# BatteryBoardV3.net
KiCad netlist of a schematic drawn in EAGLE
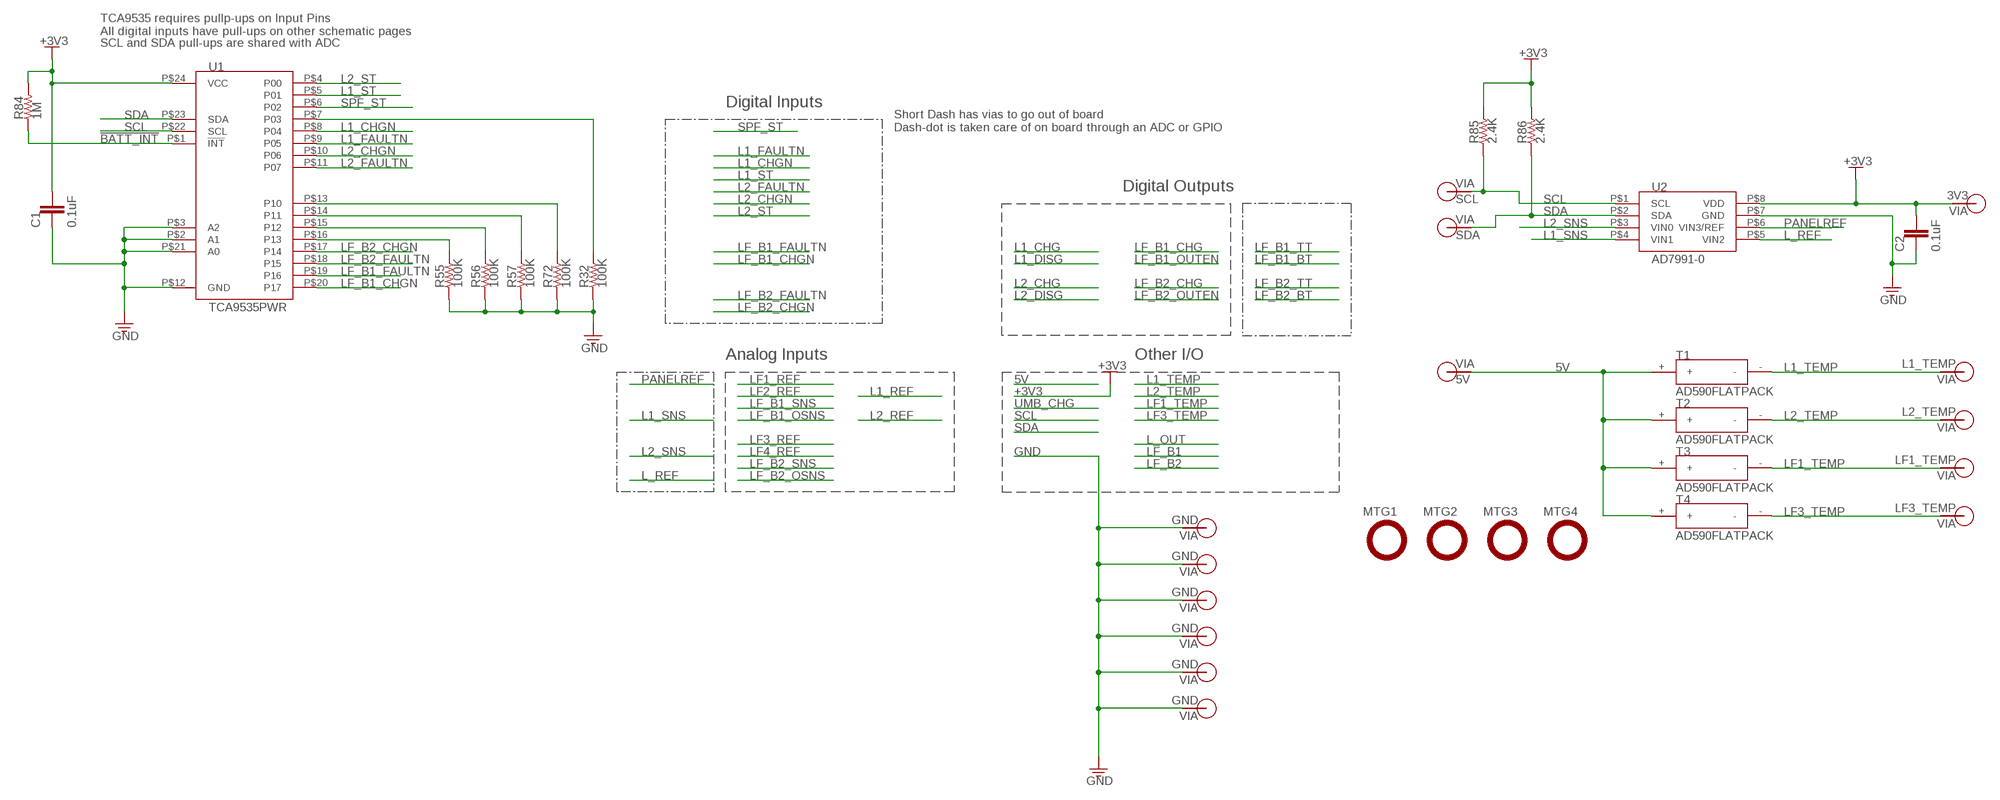
[diagram p0: schematic, sheet 1]
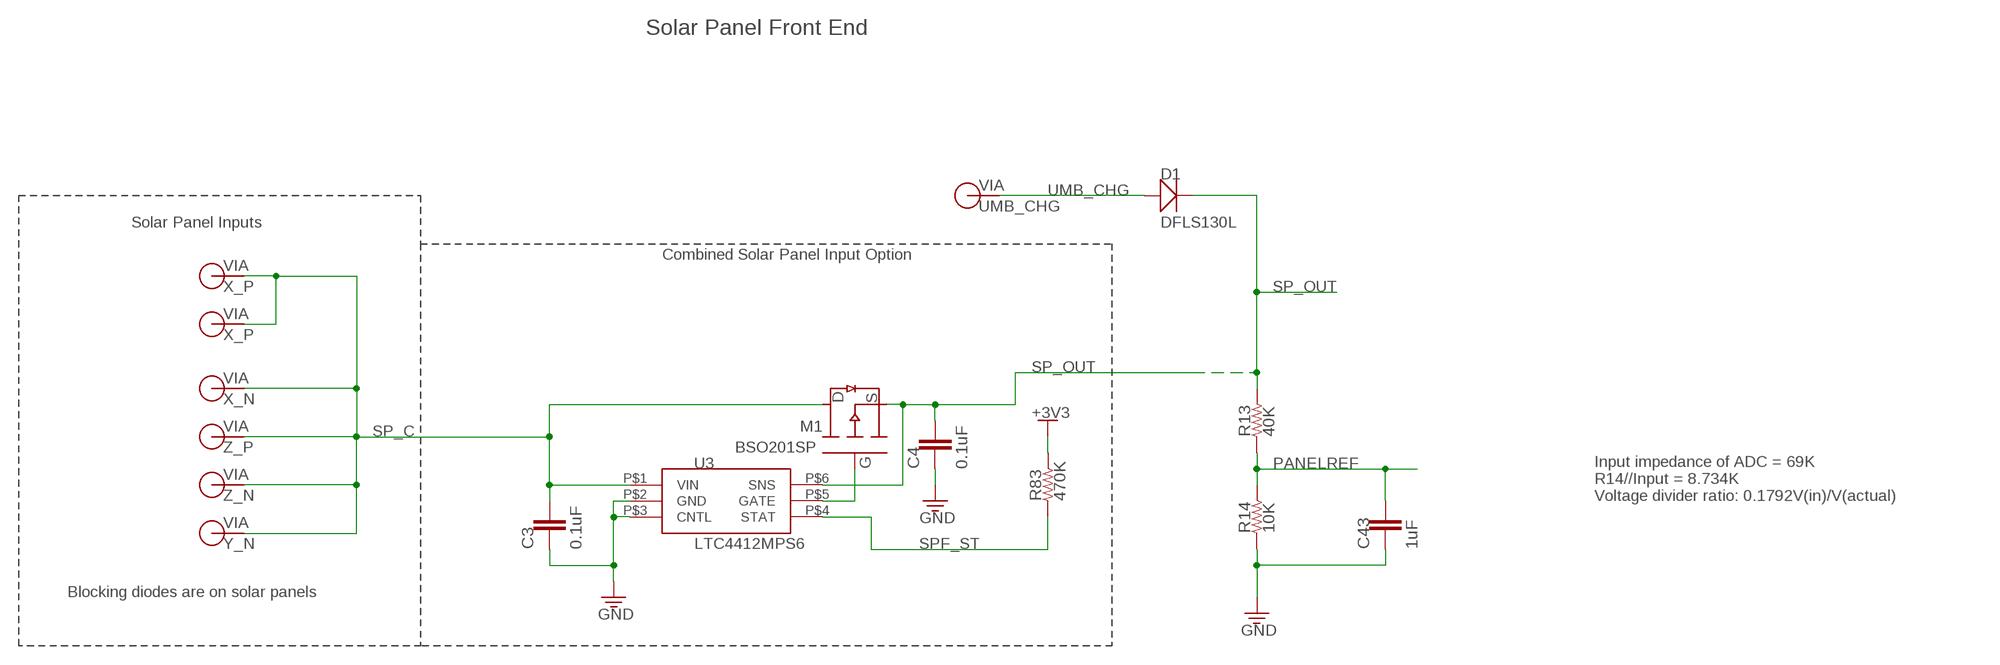
[diagram p1: schematic, sheet 2]
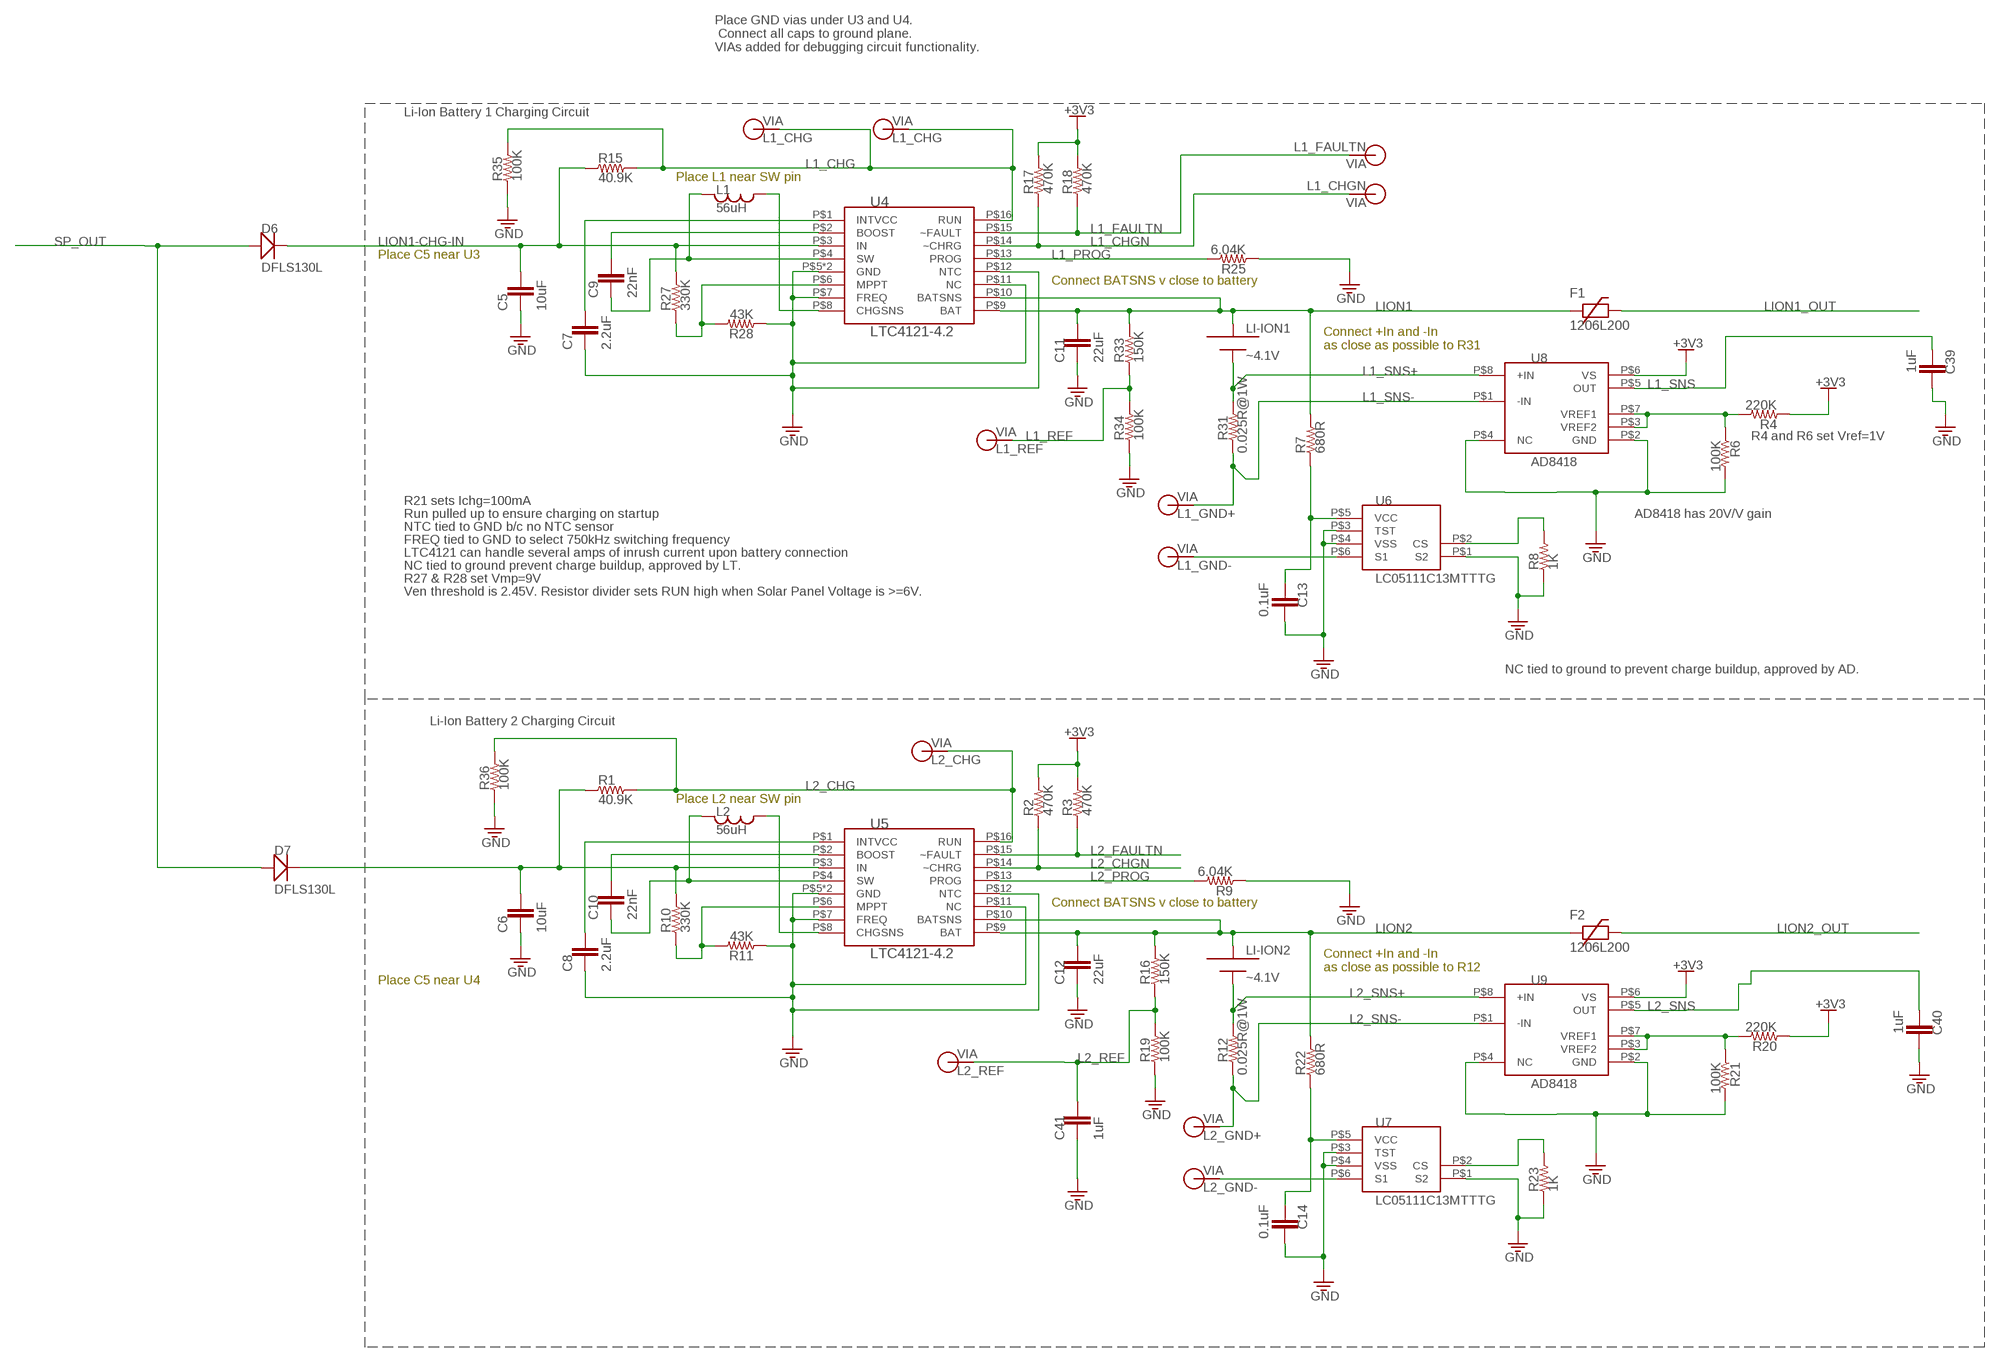
[diagram p2: schematic, sheet 3]
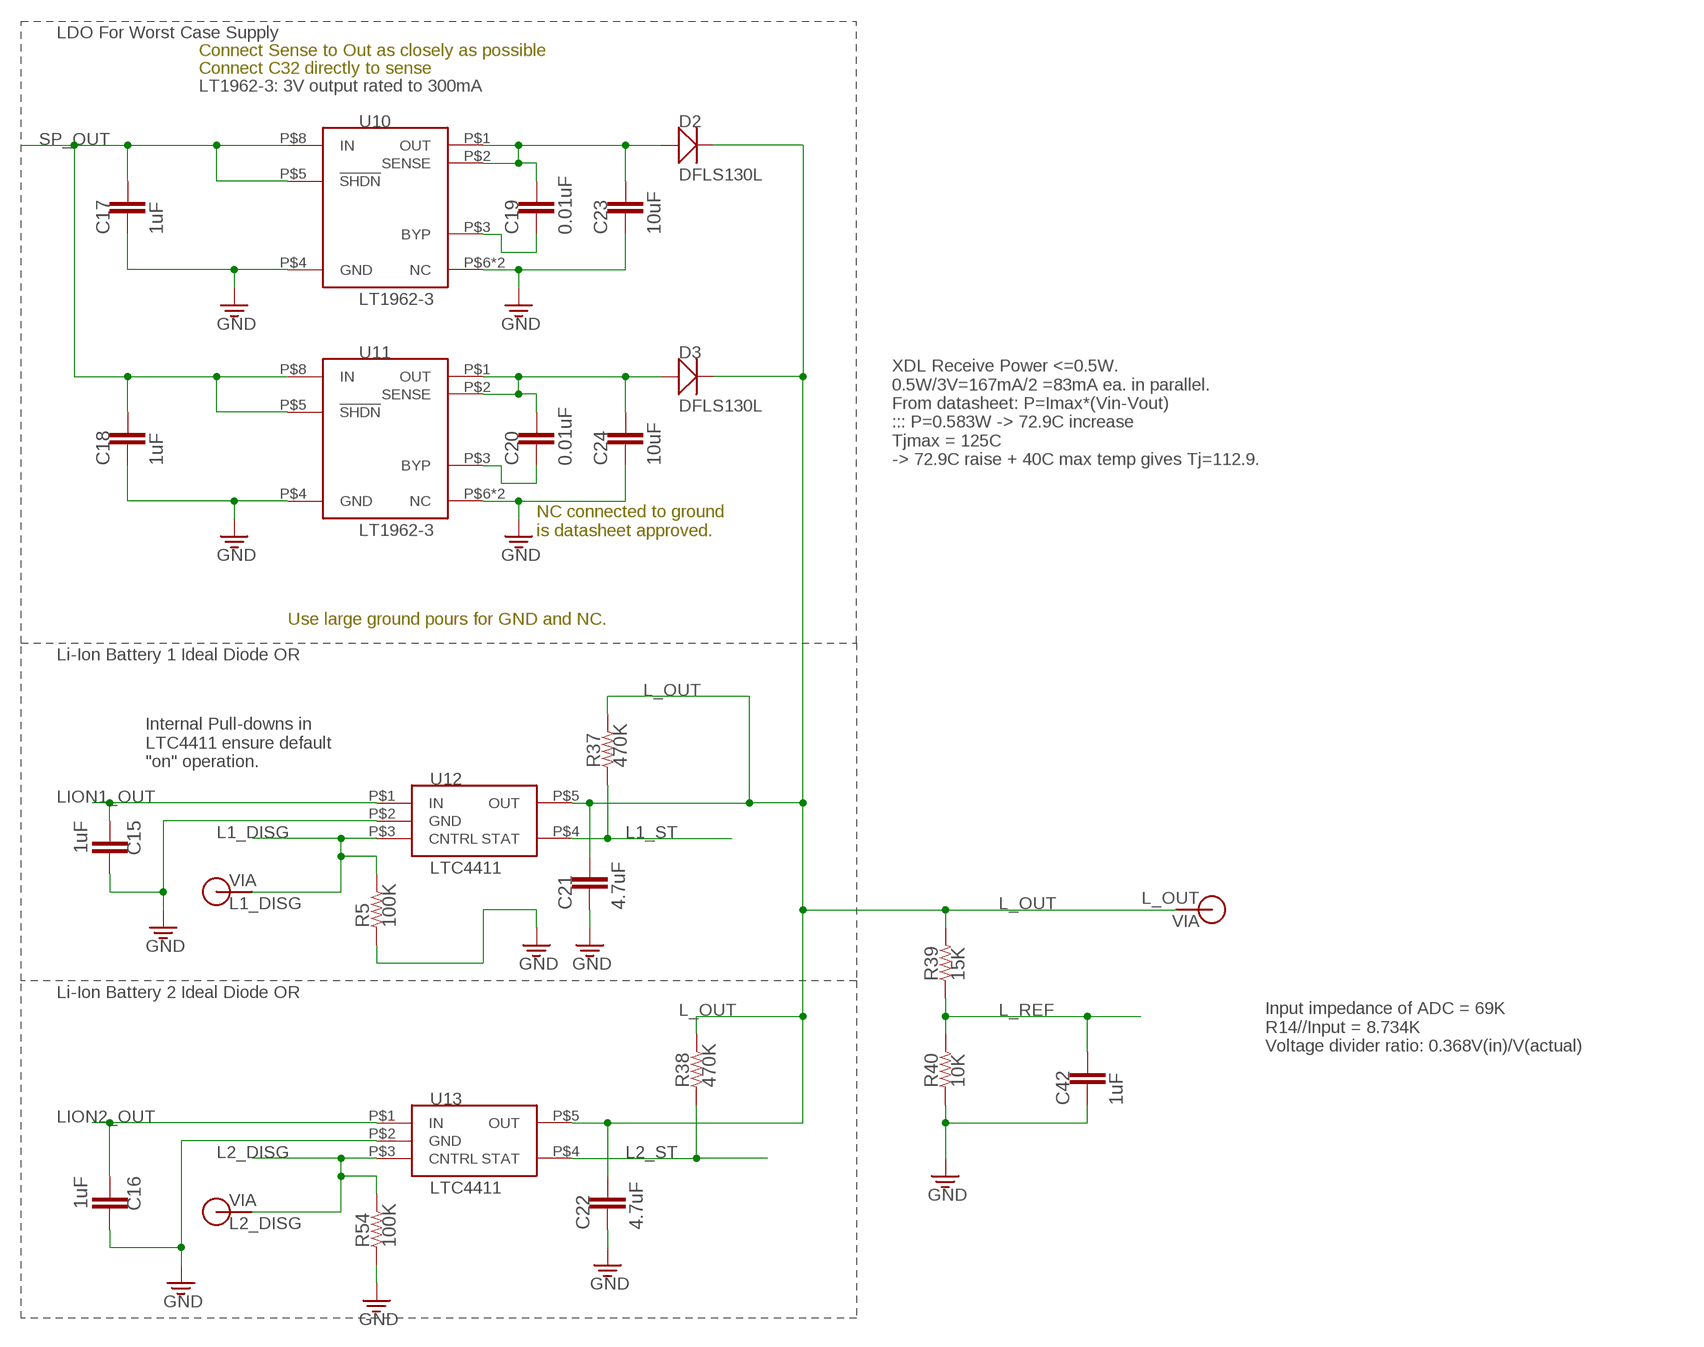
[diagram p3: schematic, sheet 4]
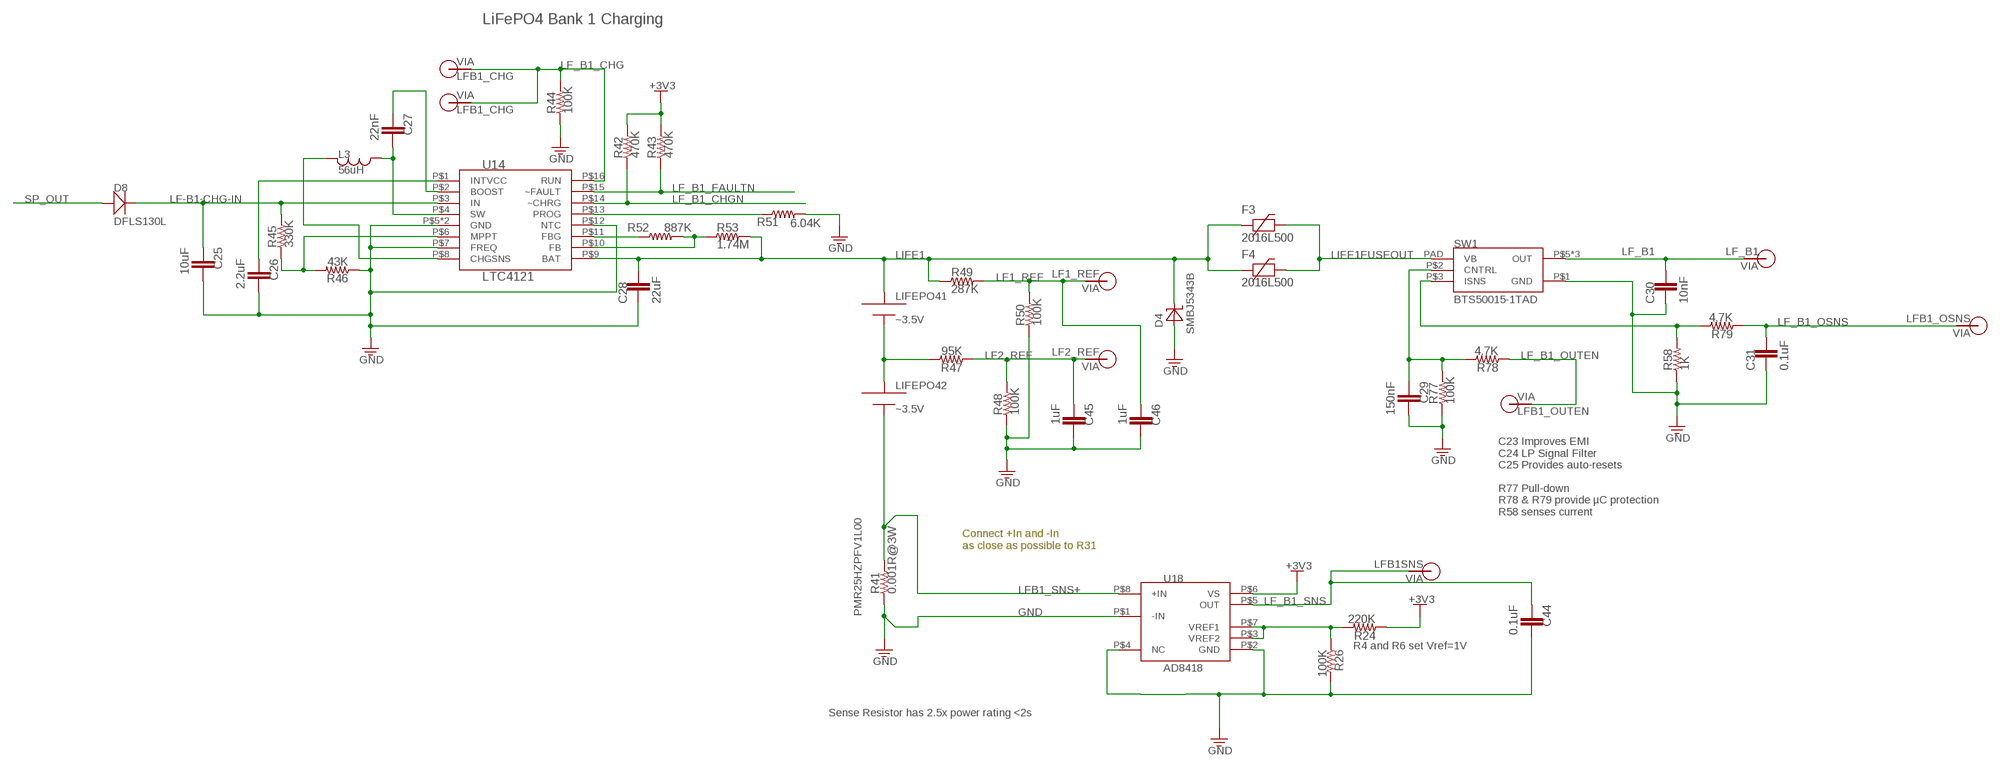
[diagram p4: schematic, sheet 5]
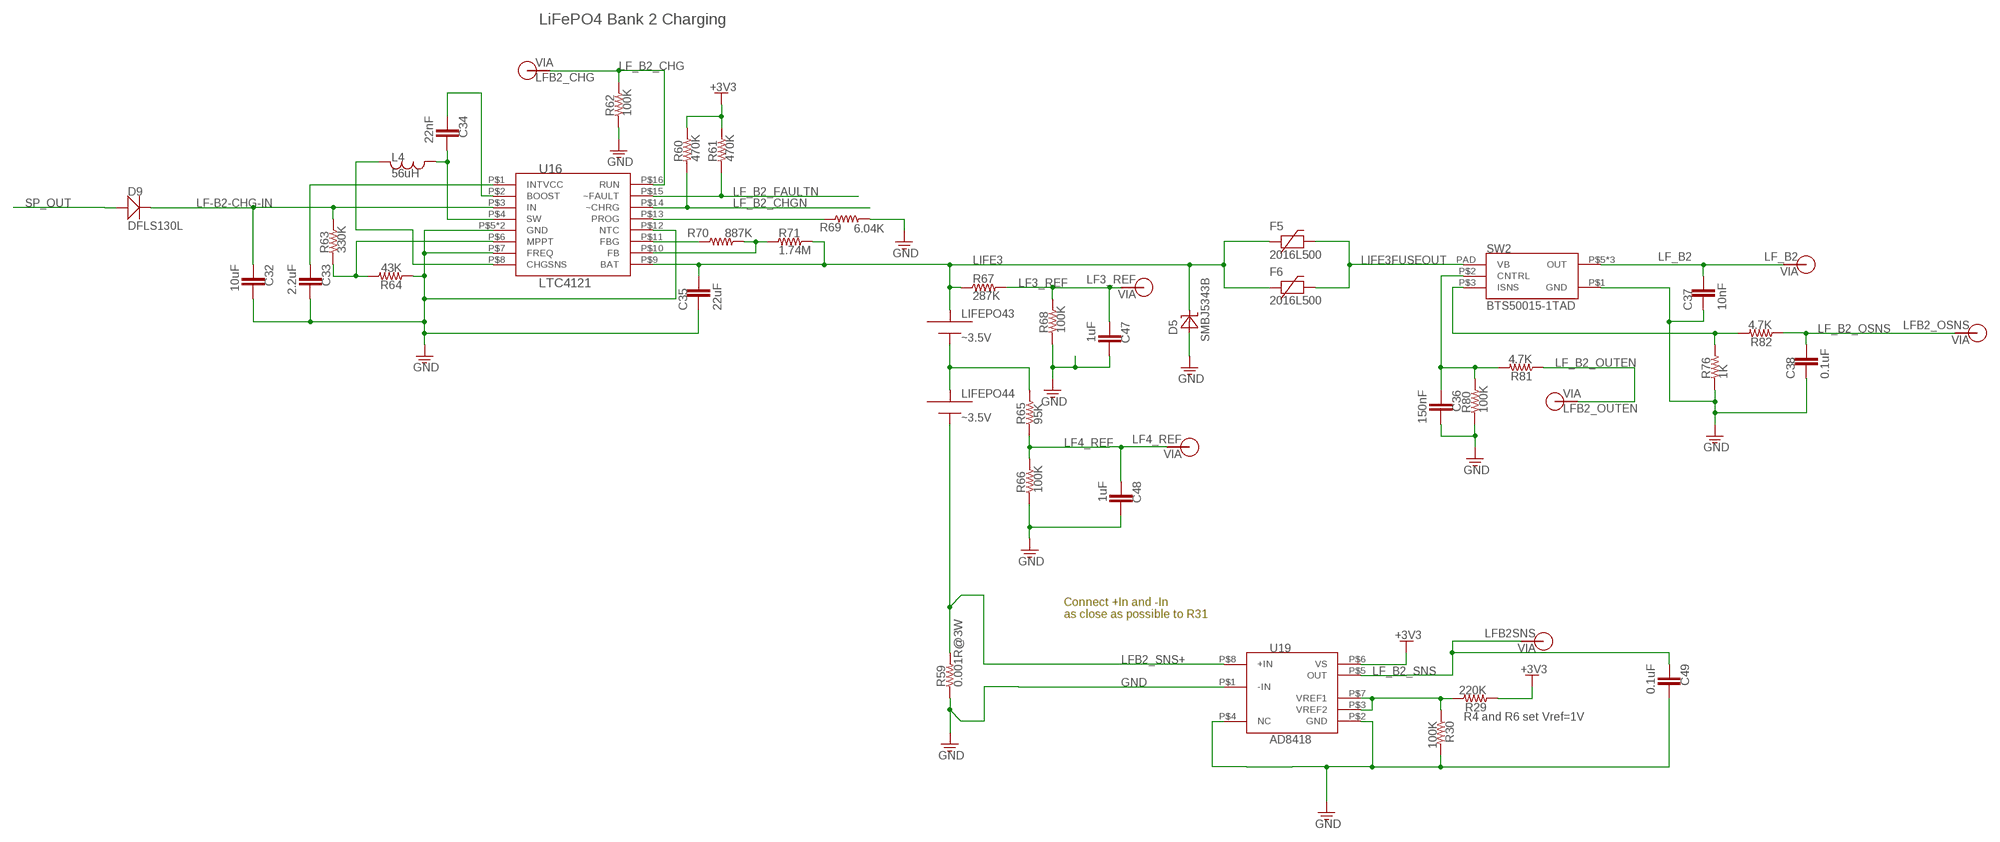
[diagram p5: schematic, sheet 6]

(export (version "E")
  (design (tool "Eeschema 10.0.6"))
  (components
    (comp (ref "C32")
      (value "10uF")
      (footprint "eagle-import:0805")
      (libsource (lib "eagle-import") (part "CAP0805"))
    )
    (comp (ref "C33")
      (value "2.2uF")
      (footprint "eagle-import:0805")
      (libsource (lib "eagle-import") (part "CAP0805"))
    )
    (comp (ref "C34")
      (value "22nF")
      (footprint "eagle-import:0805")
      (libsource (lib "eagle-import") (part "CAP0805"))
    )
    (comp (ref "C35")
      (value "22uF")
      (footprint "eagle-import:0805")
      (libsource (lib "eagle-import") (part "CAP0805"))
    )
    (comp (ref "C36")
      (value "150nF")
      (footprint "eagle-import:0805")
      (libsource (lib "eagle-import") (part "CAP0805"))
    )
    (comp (ref "C37")
      (value "10nF")
      (footprint "eagle-import:0805")
      (libsource (lib "eagle-import") (part "CAP0805"))
    )
    (comp (ref "C38")
      (value "0.1uF")
      (footprint "eagle-import:0805")
      (libsource (lib "eagle-import") (part "CAP0805"))
    )
    (comp (ref "C47")
      (value "1uF")
      (footprint "eagle-import:0805")
      (libsource (lib "eagle-import") (part "CAP0805"))
    )
    (comp (ref "C48")
      (value "1uF")
      (footprint "eagle-import:0805")
      (libsource (lib "eagle-import") (part "CAP0805"))
    )
    (comp (ref "C49")
      (value "0.1uF")
      (footprint "eagle-import:0805")
      (libsource (lib "eagle-import") (part "CAP0805"))
    )
    (comp (ref "D5")
      (value "SMBJ5343B")
      (footprint "eagle-import:DO214AA")
      (libsource (lib "eagle-import") (part "SMBJ5343B"))
    )
    (comp (ref "D9")
      (value "DFLS130L")
      (footprint "eagle-import:PWRDI-123")
      (libsource (lib "eagle-import") (part "DFLS130L"))
    )
    (comp (ref "F5")
      (value "2016L500")
      (footprint "eagle-import:2016")
      (libsource (lib "eagle-import") (part "2016L500"))
    )
    (comp (ref "F6")
      (value "2016L500")
      (footprint "eagle-import:2016")
      (libsource (lib "eagle-import") (part "2016L500"))
    )
    (comp (ref "L4")
      (value "56uH")
      (footprint "eagle-import:1812")
      (libsource (lib "eagle-import") (part "IND1812"))
    )
    (comp (ref "LIFEPO43")
      (value "~3.5V")
      (footprint "eagle-import:EQUISAT-BATTERY-VA")
      (libsource (lib "eagle-import") (part "LIFEPO4VA"))
    )
    (comp (ref "LIFEPO44")
      (value "~3.5V")
      (footprint "eagle-import:EQUISAT-BATTERY-VB")
      (libsource (lib "eagle-import") (part "LIFEPO4VB"))
    )
    (comp (ref "R29")
      (value "220K")
      (footprint "eagle-import:0805")
      (libsource (lib "eagle-import") (part "RES0805"))
    )
    (comp (ref "R30")
      (value "100K")
      (footprint "eagle-import:0805")
      (libsource (lib "eagle-import") (part "RES0805"))
    )
    (comp (ref "R59")
      (value "0.001R@3W")
      (footprint "eagle-import:1216")
      (libsource (lib "eagle-import") (part "RES"))
    )
    (comp (ref "R60")
      (value "470K")
      (footprint "eagle-import:0805")
      (libsource (lib "eagle-import") (part "RES0805"))
    )
    (comp (ref "R61")
      (value "470K")
      (footprint "eagle-import:0805")
      (libsource (lib "eagle-import") (part "RES0805"))
    )
    (comp (ref "R62")
      (value "100K")
      (footprint "eagle-import:0805")
      (libsource (lib "eagle-import") (part "RES0805"))
    )
    (comp (ref "R63")
      (value "330K")
      (footprint "eagle-import:0805")
      (libsource (lib "eagle-import") (part "RES0805"))
    )
    (comp (ref "R64")
      (value "43K")
      (footprint "eagle-import:0805")
      (libsource (lib "eagle-import") (part "RES0805"))
    )
    (comp (ref "R65")
      (value "95K")
      (footprint "eagle-import:0805")
      (libsource (lib "eagle-import") (part "RES0805"))
    )
    (comp (ref "R66")
      (value "100K")
      (footprint "eagle-import:0805")
      (libsource (lib "eagle-import") (part "RES0805"))
    )
    (comp (ref "R67")
      (value "287K")
      (footprint "eagle-import:0805")
      (libsource (lib "eagle-import") (part "RES0805"))
    )
    (comp (ref "R68")
      (value "100K")
      (footprint "eagle-import:0805")
      (libsource (lib "eagle-import") (part "RES0805"))
    )
    (comp (ref "R69")
      (value "6.04K")
      (footprint "eagle-import:0805")
      (libsource (lib "eagle-import") (part "RES0805"))
    )
    (comp (ref "R70")
      (value "887K")
      (footprint "eagle-import:0805")
      (libsource (lib "eagle-import") (part "RES0805"))
    )
    (comp (ref "R71")
      (value "1.74M")
      (footprint "eagle-import:0805")
      (libsource (lib "eagle-import") (part "RES0805"))
    )
    (comp (ref "R76")
      (value "1K")
      (footprint "eagle-import:0805")
      (libsource (lib "eagle-import") (part "RES0805"))
    )
    (comp (ref "R80")
      (value "100K")
      (footprint "eagle-import:0805")
      (libsource (lib "eagle-import") (part "RES0805"))
    )
    (comp (ref "R81")
      (value "4.7K")
      (footprint "eagle-import:0805")
      (libsource (lib "eagle-import") (part "RES0805"))
    )
    (comp (ref "R82")
      (value "4.7K")
      (footprint "eagle-import:0805")
      (libsource (lib "eagle-import") (part "RES0805"))
    )
    (comp (ref "SW2")
      (value "BTS50015-1TAD")
      (footprint "eagle-import:TO-263-7-8")
      (libsource (lib "eagle-import") (part "BTS50015-1TAD"))
    )
    (comp (ref "U16")
      (value "LTC4121")
      (footprint "eagle-import:QFN-16-PAD")
      (libsource (lib "eagle-import") (part "LTC4121"))
    )
    (comp (ref "U19")
      (value "AD8418")
      (footprint "eagle-import:MSOP-8")
      (libsource (lib "eagle-import") (part "AD8418"))
    )
    (comp (ref "V44")
      (value "LFB2SNS")
      (footprint "eagle-import:VIA-60MIL")
      (libsource (lib "eagle-import") (part "VIA-60MIL"))
    )
    (comp (ref "V47")
      (value "LFB2_CHG")
      (footprint "eagle-import:VIA-60MIL")
      (libsource (lib "eagle-import") (part "VIA-60MIL"))
    )
    (comp (ref "V49")
      (value "LF3_REF")
      (footprint "eagle-import:VIA-60MIL")
      (libsource (lib "eagle-import") (part "VIA-60MIL"))
    )
    (comp (ref "V50")
      (value "LF4_REF")
      (footprint "eagle-import:VIA-60MIL")
      (libsource (lib "eagle-import") (part "VIA-60MIL"))
    )
    (comp (ref "V51")
      (value "LFB2_OUTEN")
      (footprint "eagle-import:VIA-60MIL")
      (libsource (lib "eagle-import") (part "VIA-60MIL"))
    )
    (comp (ref "V53")
      (value "LF_B2")
      (footprint "eagle-import:VIA-120MIL")
      (libsource (lib "eagle-import") (part "VIA-120MIL"))
    )
    (comp (ref "V99")
      (value "LFB2_OSNS")
      (footprint "eagle-import:VIA-60MIL")
      (libsource (lib "eagle-import") (part "VIA-60MIL"))
    )
    (comp (ref "C1")
      (value "0.1uF")
      (footprint "eagle-import:0805")
      (libsource (lib "eagle-import") (part "CAP0805"))
    )
    (comp (ref "C2")
      (value "0.1uF")
      (footprint "eagle-import:0805")
      (libsource (lib "eagle-import") (part "CAP0805"))
    )
    (comp (ref "MTG1")
      (value "MTG-NPTH-#2-CLOSE")
      (footprint "eagle-import:#2-CLOSE-NPTH")
      (libsource (lib "eagle-import") (part "MTG-NPTH-#2-CLOSE"))
    )
    (comp (ref "MTG2")
      (value "MTG-NPTH-#2-CLOSE")
      (footprint "eagle-import:#2-CLOSE-NPTH")
      (libsource (lib "eagle-import") (part "MTG-NPTH-#2-CLOSE"))
    )
    (comp (ref "MTG3")
      (value "MTG-NPTH-#2-CLOSE")
      (footprint "eagle-import:#2-CLOSE-NPTH")
      (libsource (lib "eagle-import") (part "MTG-NPTH-#2-CLOSE"))
    )
    (comp (ref "MTG4")
      (value "MTG-NPTH-#2-CLOSE")
      (footprint "eagle-import:#2-CLOSE-NPTH")
      (libsource (lib "eagle-import") (part "MTG-NPTH-#2-CLOSE"))
    )
    (comp (ref "R32")
      (value "100K")
      (footprint "eagle-import:0805")
      (libsource (lib "eagle-import") (part "RES0805"))
    )
    (comp (ref "R55")
      (value "100K")
      (footprint "eagle-import:0805")
      (libsource (lib "eagle-import") (part "RES0805"))
    )
    (comp (ref "R56")
      (value "100K")
      (footprint "eagle-import:0805")
      (libsource (lib "eagle-import") (part "RES0805"))
    )
    (comp (ref "R57")
      (value "100K")
      (footprint "eagle-import:0805")
      (libsource (lib "eagle-import") (part "RES0805"))
    )
    (comp (ref "R72")
      (value "100K")
      (footprint "eagle-import:0805")
      (libsource (lib "eagle-import") (part "RES0805"))
    )
    (comp (ref "R84")
      (value "1M")
      (footprint "eagle-import:0805")
      (libsource (lib "eagle-import") (part "RES0805"))
    )
    (comp (ref "R85")
      (value "2.4K")
      (footprint "eagle-import:0805")
      (libsource (lib "eagle-import") (part "RES0805"))
    )
    (comp (ref "R86")
      (value "2.4K")
      (footprint "eagle-import:0805")
      (libsource (lib "eagle-import") (part "RES0805"))
    )
    (comp (ref "T1")
      (value "AD590FLATPACK")
      (footprint "eagle-import:FLATPACK")
      (libsource (lib "eagle-import") (part "AD590FLATPACK"))
    )
    (comp (ref "T2")
      (value "AD590FLATPACK")
      (footprint "eagle-import:FLATPACK")
      (libsource (lib "eagle-import") (part "AD590FLATPACK"))
    )
    (comp (ref "T3")
      (value "AD590FLATPACK")
      (footprint "eagle-import:FLATPACK")
      (libsource (lib "eagle-import") (part "AD590FLATPACK"))
    )
    (comp (ref "T4")
      (value "AD590FLATPACK")
      (footprint "eagle-import:FLATPACK")
      (libsource (lib "eagle-import") (part "AD590FLATPACK"))
    )
    (comp (ref "U1")
      (value "TCA9535PWR")
      (footprint "eagle-import:TSSOP-24")
      (libsource (lib "eagle-import") (part "TCA9535PWR"))
    )
    (comp (ref "U2")
      (value "AD7991-0")
      (footprint "eagle-import:SOT-23-8")
      (libsource (lib "eagle-import") (part "AD7991-0"))
    )
    (comp (ref "V1")
      (value "GND")
      (footprint "eagle-import:VIA-120MIL")
      (libsource (lib "eagle-import") (part "VIA-120MIL"))
    )
    (comp (ref "V2")
      (value "GND")
      (footprint "eagle-import:VIA-120MIL")
      (libsource (lib "eagle-import") (part "VIA-120MIL"))
    )
    (comp (ref "V3")
      (value "GND")
      (footprint "eagle-import:VIA-60MIL-SQ")
      (libsource (lib "eagle-import") (part "VIA60MIL-SQ"))
    )
    (comp (ref "V4")
      (value "GND")
      (footprint "eagle-import:VIA-120MIL")
      (libsource (lib "eagle-import") (part "VIA-120MIL"))
    )
    (comp (ref "V5")
      (value "SCL")
      (footprint "eagle-import:VIA-60MIL")
      (libsource (lib "eagle-import") (part "VIA-60MIL"))
    )
    (comp (ref "V6")
      (value "SDA")
      (footprint "eagle-import:VIA-60MIL")
      (libsource (lib "eagle-import") (part "VIA-60MIL"))
    )
    (comp (ref "V7")
      (value "5V")
      (footprint "eagle-import:VIA-60MIL")
      (libsource (lib "eagle-import") (part "VIA-60MIL"))
    )
    (comp (ref "V8")
      (value "L1_TEMP")
      (footprint "eagle-import:VIA-60MIL")
      (libsource (lib "eagle-import") (part "VIA-60MIL"))
    )
    (comp (ref "V9")
      (value "L2_TEMP")
      (footprint "eagle-import:VIA-60MIL")
      (libsource (lib "eagle-import") (part "VIA-60MIL"))
    )
    (comp (ref "V10")
      (value "LF1_TEMP")
      (footprint "eagle-import:VIA-60MIL")
      (libsource (lib "eagle-import") (part "VIA-60MIL"))
    )
    (comp (ref "V11")
      (value "LF3_TEMP")
      (footprint "eagle-import:VIA-60MIL")
      (libsource (lib "eagle-import") (part "VIA-60MIL"))
    )
    (comp (ref "V12")
      (value "3V3")
      (footprint "eagle-import:VIA-60MIL")
      (libsource (lib "eagle-import") (part "VIA-60MIL"))
    )
    (comp (ref "V28")
      (value "GND")
      (footprint "eagle-import:VIA-60MIL-SQ")
      (libsource (lib "eagle-import") (part "VIA60MIL-SQ"))
    )
    (comp (ref "V36")
      (value "GND")
      (footprint "eagle-import:VIA-60MIL-SQ")
      (libsource (lib "eagle-import") (part "VIA60MIL-SQ"))
    )
    (comp (ref "C5")
      (value "10uF")
      (footprint "eagle-import:0805")
      (libsource (lib "eagle-import") (part "CAP0805"))
    )
    (comp (ref "C6")
      (value "10uF")
      (footprint "eagle-import:0805")
      (libsource (lib "eagle-import") (part "CAP0805"))
    )
    (comp (ref "C7")
      (value "2.2uF")
      (footprint "eagle-import:0805")
      (libsource (lib "eagle-import") (part "CAP0805"))
    )
    (comp (ref "C8")
      (value "2.2uF")
      (footprint "eagle-import:0805")
      (libsource (lib "eagle-import") (part "CAP0805"))
    )
    (comp (ref "C9")
      (value "22nF")
      (footprint "eagle-import:0805")
      (libsource (lib "eagle-import") (part "CAP0805"))
    )
    (comp (ref "C10")
      (value "22nF")
      (footprint "eagle-import:0805")
      (libsource (lib "eagle-import") (part "CAP0805"))
    )
    (comp (ref "C11")
      (value "22uF")
      (footprint "eagle-import:0805")
      (libsource (lib "eagle-import") (part "CAP0805"))
    )
    (comp (ref "C12")
      (value "22uF")
      (footprint "eagle-import:0805")
      (libsource (lib "eagle-import") (part "CAP0805"))
    )
    (comp (ref "C13")
      (value "0.1uF")
      (footprint "eagle-import:0805")
      (libsource (lib "eagle-import") (part "CAP0805"))
    )
    (comp (ref "C14")
      (value "0.1uF")
      (footprint "eagle-import:0805")
      (libsource (lib "eagle-import") (part "CAP0805"))
    )
    (comp (ref "C39")
      (value "1uF")
      (footprint "eagle-import:0805")
      (libsource (lib "eagle-import") (part "CAP0805"))
    )
    (comp (ref "C40")
      (value "1uF")
      (footprint "eagle-import:0805")
      (libsource (lib "eagle-import") (part "CAP0805"))
    )
    (comp (ref "C41")
      (value "1uF")
      (footprint "eagle-import:0805")
      (libsource (lib "eagle-import") (part "CAP0805"))
    )
    (comp (ref "D6")
      (value "DFLS130L")
      (footprint "eagle-import:PWRDI-123")
      (libsource (lib "eagle-import") (part "DFLS130L"))
    )
    (comp (ref "D7")
      (value "DFLS130L")
      (footprint "eagle-import:PWRDI-123")
      (libsource (lib "eagle-import") (part "DFLS130L"))
    )
    (comp (ref "F1")
      (value "1206L200")
      (footprint "eagle-import:1206")
      (libsource (lib "eagle-import") (part "PTCFUSE1206"))
    )
    (comp (ref "F2")
      (value "1206L200")
      (footprint "eagle-import:1206")
      (libsource (lib "eagle-import") (part "PTCFUSE1206"))
    )
    (comp (ref "L1")
      (value "56uH")
      (footprint "eagle-import:1812")
      (libsource (lib "eagle-import") (part "IND1812"))
    )
    (comp (ref "L2")
      (value "56uH")
      (footprint "eagle-import:1812")
      (libsource (lib "eagle-import") (part "IND1812"))
    )
    (comp (ref "LI-ION1")
      (value "~4.1V")
      (footprint "eagle-import:EQUISAT-BATTERY-VA")
      (libsource (lib "eagle-import") (part "LI-ION"))
    )
    (comp (ref "LI-ION2")
      (value "~4.1V")
      (footprint "eagle-import:EQUISAT-BATTERY-VA")
      (libsource (lib "eagle-import") (part "LI-ION"))
    )
    (comp (ref "R1")
      (value "40.9K")
      (footprint "eagle-import:0805")
      (libsource (lib "eagle-import") (part "RES0805"))
    )
    (comp (ref "R2")
      (value "470K")
      (footprint "eagle-import:0805")
      (libsource (lib "eagle-import") (part "RES0805"))
    )
    (comp (ref "R3")
      (value "470K")
      (footprint "eagle-import:0805")
      (libsource (lib "eagle-import") (part "RES0805"))
    )
    (comp (ref "R4")
      (value "220K")
      (footprint "eagle-import:0805")
      (libsource (lib "eagle-import") (part "RES0805"))
    )
    (comp (ref "R6")
      (value "100K")
      (footprint "eagle-import:0805")
      (libsource (lib "eagle-import") (part "RES0805"))
    )
    (comp (ref "R7")
      (value "680R")
      (footprint "eagle-import:0805")
      (libsource (lib "eagle-import") (part "RES0805"))
    )
    (comp (ref "R8")
      (value "1K")
      (footprint "eagle-import:0805")
      (libsource (lib "eagle-import") (part "RES0805"))
    )
    (comp (ref "R9")
      (value "6.04K")
      (footprint "eagle-import:0805")
      (libsource (lib "eagle-import") (part "RES0805"))
    )
    (comp (ref "R10")
      (value "330K")
      (footprint "eagle-import:0805")
      (libsource (lib "eagle-import") (part "RES0805"))
    )
    (comp (ref "R11")
      (value "43K")
      (footprint "eagle-import:0805")
      (libsource (lib "eagle-import") (part "RES0805"))
    )
    (comp (ref "R12")
      (value "0.025R@1W")
      (footprint "eagle-import:1210")
      (libsource (lib "eagle-import") (part "RES1210"))
    )
    (comp (ref "R15")
      (value "40.9K")
      (footprint "eagle-import:0805")
      (libsource (lib "eagle-import") (part "RES0805"))
    )
    (comp (ref "R16")
      (value "150K")
      (footprint "eagle-import:0805")
      (libsource (lib "eagle-import") (part "RES0805"))
    )
    (comp (ref "R17")
      (value "470K")
      (footprint "eagle-import:0805")
      (libsource (lib "eagle-import") (part "RES0805"))
    )
    (comp (ref "R18")
      (value "470K")
      (footprint "eagle-import:0805")
      (libsource (lib "eagle-import") (part "RES0805"))
    )
    (comp (ref "R19")
      (value "100K")
      (footprint "eagle-import:0805")
      (libsource (lib "eagle-import") (part "RES0805"))
    )
    (comp (ref "R20")
      (value "220K")
      (footprint "eagle-import:0805")
      (libsource (lib "eagle-import") (part "RES0805"))
    )
    (comp (ref "R21")
      (value "100K")
      (footprint "eagle-import:0805")
      (libsource (lib "eagle-import") (part "RES0805"))
    )
    (comp (ref "R22")
      (value "680R")
      (footprint "eagle-import:0805")
      (libsource (lib "eagle-import") (part "RES0805"))
    )
    (comp (ref "R23")
      (value "1K")
      (footprint "eagle-import:0805")
      (libsource (lib "eagle-import") (part "RES0805"))
    )
    (comp (ref "R25")
      (value "6.04K")
      (footprint "eagle-import:0805")
      (libsource (lib "eagle-import") (part "RES0805"))
    )
    (comp (ref "R27")
      (value "330K")
      (footprint "eagle-import:0805")
      (libsource (lib "eagle-import") (part "RES0805"))
    )
    (comp (ref "R28")
      (value "43K")
      (footprint "eagle-import:0805")
      (libsource (lib "eagle-import") (part "RES0805"))
    )
    (comp (ref "R31")
      (value "0.025R@1W")
      (footprint "eagle-import:1210")
      (libsource (lib "eagle-import") (part "RES1210"))
    )
    (comp (ref "R33")
      (value "150K")
      (footprint "eagle-import:0805")
      (libsource (lib "eagle-import") (part "RES0805"))
    )
    (comp (ref "R34")
      (value "100K")
      (footprint "eagle-import:0805")
      (libsource (lib "eagle-import") (part "RES0805"))
    )
    (comp (ref "R35")
      (value "100K")
      (footprint "eagle-import:0805")
      (libsource (lib "eagle-import") (part "RES0805"))
    )
    (comp (ref "R36")
      (value "100K")
      (footprint "eagle-import:0805")
      (libsource (lib "eagle-import") (part "RES0805"))
    )
    (comp (ref "U4")
      (value "LTC4121-4.2")
      (footprint "eagle-import:QFN-16-PAD")
      (libsource (lib "eagle-import") (part "LTC4121-4.2"))
    )
    (comp (ref "U5")
      (value "LTC4121-4.2")
      (footprint "eagle-import:QFN-16-PAD")
      (libsource (lib "eagle-import") (part "LTC4121-4.2"))
    )
    (comp (ref "U6")
      (value "LC05111C13MTTTG")
      (footprint "eagle-import:WDFN6")
      (libsource (lib "eagle-import") (part "LC05111C13MTTTG"))
    )
    (comp (ref "U7")
      (value "LC05111C13MTTTG")
      (footprint "eagle-import:WDFN6")
      (libsource (lib "eagle-import") (part "LC05111C13MTTTG"))
    )
    (comp (ref "U8")
      (value "AD8418")
      (footprint "eagle-import:MSOP-8")
      (libsource (lib "eagle-import") (part "AD8418"))
    )
    (comp (ref "U9")
      (value "AD8418")
      (footprint "eagle-import:MSOP-8")
      (libsource (lib "eagle-import") (part "AD8418"))
    )
    (comp (ref "V20")
      (value "L1_CHG")
      (footprint "eagle-import:VIA-60MIL")
      (libsource (lib "eagle-import") (part "VIA-60MIL"))
    )
    (comp (ref "V21")
      (value "L1_REF")
      (footprint "eagle-import:VIA-60MIL")
      (libsource (lib "eagle-import") (part "VIA-60MIL"))
    )
    (comp (ref "V22")
      (value "L1_GND+")
      (footprint "eagle-import:VIA-60MIL")
      (libsource (lib "eagle-import") (part "VIA-60MIL"))
    )
    (comp (ref "V23")
      (value "L1_GND-")
      (footprint "eagle-import:VIA-60MIL")
      (libsource (lib "eagle-import") (part "VIA-60MIL"))
    )
    (comp (ref "V24")
      (value "L2_GND+")
      (footprint "eagle-import:VIA-60MIL")
      (libsource (lib "eagle-import") (part "VIA-60MIL"))
    )
    (comp (ref "V25")
      (value "L2_GND-")
      (footprint "eagle-import:VIA-60MIL")
      (libsource (lib "eagle-import") (part "VIA-60MIL"))
    )
    (comp (ref "V26")
      (value "L1_FAULTN")
      (footprint "eagle-import:VIA-60MIL-SQ")
      (libsource (lib "eagle-import") (part "VIA60MIL-SQ"))
    )
    (comp (ref "V27")
      (value "L1_CHGN")
      (footprint "eagle-import:VIA-60MIL-SQ")
      (libsource (lib "eagle-import") (part "VIA60MIL-SQ"))
    )
    (comp (ref "V31")
      (value "L2_REF")
      (footprint "eagle-import:VIA-60MIL")
      (libsource (lib "eagle-import") (part "VIA-60MIL"))
    )
    (comp (ref "V33")
      (value "L2_CHG")
      (footprint "eagle-import:VIA-60MIL")
      (libsource (lib "eagle-import") (part "VIA-60MIL"))
    )
    (comp (ref "V48")
      (value "L1_CHG")
      (footprint "eagle-import:VIA-60MIL-SQ")
      (libsource (lib "eagle-import") (part "VIA60MIL-SQ"))
    )
    (comp (ref "C25")
      (value "10uF")
      (footprint "eagle-import:0805")
      (libsource (lib "eagle-import") (part "CAP0805"))
    )
    (comp (ref "C26")
      (value "2.2uF")
      (footprint "eagle-import:0805")
      (libsource (lib "eagle-import") (part "CAP0805"))
    )
    (comp (ref "C27")
      (value "22nF")
      (footprint "eagle-import:0805")
      (libsource (lib "eagle-import") (part "CAP0805"))
    )
    (comp (ref "C28")
      (value "22uF")
      (footprint "eagle-import:0805")
      (libsource (lib "eagle-import") (part "CAP0805"))
    )
    (comp (ref "C29")
      (value "150nF")
      (footprint "eagle-import:0805")
      (libsource (lib "eagle-import") (part "CAP0805"))
    )
    (comp (ref "C30")
      (value "10nF")
      (footprint "eagle-import:0805")
      (libsource (lib "eagle-import") (part "CAP0805"))
    )
    (comp (ref "C31")
      (value "0.1uF")
      (footprint "eagle-import:0805")
      (libsource (lib "eagle-import") (part "CAP0805"))
    )
    (comp (ref "C44")
      (value "0.1uF")
      (footprint "eagle-import:0805")
      (libsource (lib "eagle-import") (part "CAP0805"))
    )
    (comp (ref "C45")
      (value "1uF")
      (footprint "eagle-import:0805")
      (libsource (lib "eagle-import") (part "CAP0805"))
    )
    (comp (ref "C46")
      (value "1uF")
      (footprint "eagle-import:0805")
      (libsource (lib "eagle-import") (part "CAP0805"))
    )
    (comp (ref "D4")
      (value "SMBJ5343B")
      (footprint "eagle-import:DO214AA")
      (libsource (lib "eagle-import") (part "SMBJ5343B"))
    )
    (comp (ref "D8")
      (value "DFLS130L")
      (footprint "eagle-import:PWRDI-123")
      (libsource (lib "eagle-import") (part "DFLS130L"))
    )
    (comp (ref "F3")
      (value "2016L500")
      (footprint "eagle-import:2016")
      (libsource (lib "eagle-import") (part "2016L500"))
    )
    (comp (ref "F4")
      (value "2016L500")
      (footprint "eagle-import:2016")
      (libsource (lib "eagle-import") (part "2016L500"))
    )
    (comp (ref "L3")
      (value "56uH")
      (footprint "eagle-import:1812")
      (libsource (lib "eagle-import") (part "IND1812"))
    )
    (comp (ref "LIFEPO41")
      (value "~3.5V")
      (footprint "eagle-import:EQUISAT-BATTERY-VA")
      (libsource (lib "eagle-import") (part "LIFEPO4VA"))
    )
    (comp (ref "LIFEPO42")
      (value "~3.5V")
      (footprint "eagle-import:EQUISAT-BATTERY-VB")
      (libsource (lib "eagle-import") (part "LIFEPO4VB"))
    )
    (comp (ref "R24")
      (value "220K")
      (footprint "eagle-import:0805")
      (libsource (lib "eagle-import") (part "RES0805"))
    )
    (comp (ref "R26")
      (value "100K")
      (footprint "eagle-import:0805")
      (libsource (lib "eagle-import") (part "RES0805"))
    )
    (comp (ref "R41")
      (value "0.001R@3W")
      (footprint "eagle-import:1216")
      (libsource (lib "eagle-import") (part "RES"))
    )
    (comp (ref "R42")
      (value "470K")
      (footprint "eagle-import:0805")
      (libsource (lib "eagle-import") (part "RES0805"))
    )
    (comp (ref "R43")
      (value "470K")
      (footprint "eagle-import:0805")
      (libsource (lib "eagle-import") (part "RES0805"))
    )
    (comp (ref "R44")
      (value "100K")
      (footprint "eagle-import:0805")
      (libsource (lib "eagle-import") (part "RES0805"))
    )
    (comp (ref "R45")
      (value "330K")
      (footprint "eagle-import:0805")
      (libsource (lib "eagle-import") (part "RES0805"))
    )
    (comp (ref "R46")
      (value "43K")
      (footprint "eagle-import:0805")
      (libsource (lib "eagle-import") (part "RES0805"))
    )
    (comp (ref "R47")
      (value "95K")
      (footprint "eagle-import:0805")
      (libsource (lib "eagle-import") (part "RES0805"))
    )
    (comp (ref "R48")
      (value "100K")
      (footprint "eagle-import:0805")
      (libsource (lib "eagle-import") (part "RES0805"))
    )
    (comp (ref "R49")
      (value "287K")
      (footprint "eagle-import:0805")
      (libsource (lib "eagle-import") (part "RES0805"))
    )
    (comp (ref "R50")
      (value "100K")
      (footprint "eagle-import:0805")
      (libsource (lib "eagle-import") (part "RES0805"))
    )
    (comp (ref "R51")
      (value "6.04K")
      (footprint "eagle-import:0805")
      (libsource (lib "eagle-import") (part "RES0805"))
    )
    (comp (ref "R52")
      (value "887K")
      (footprint "eagle-import:0805")
      (libsource (lib "eagle-import") (part "RES0805"))
    )
    (comp (ref "R53")
      (value "1.74M")
      (footprint "eagle-import:0805")
      (libsource (lib "eagle-import") (part "RES0805"))
    )
    (comp (ref "R58")
      (value "1K")
      (footprint "eagle-import:0805")
      (libsource (lib "eagle-import") (part "RES0805"))
    )
    (comp (ref "R77")
      (value "100K")
      (footprint "eagle-import:0805")
      (libsource (lib "eagle-import") (part "RES0805"))
    )
    (comp (ref "R78")
      (value "4.7K")
      (footprint "eagle-import:0805")
      (libsource (lib "eagle-import") (part "RES0805"))
    )
    (comp (ref "R79")
      (value "4.7K")
      (footprint "eagle-import:0805")
      (libsource (lib "eagle-import") (part "RES0805"))
    )
    (comp (ref "SW1")
      (value "BTS50015-1TAD")
      (footprint "eagle-import:TO-263-7-8")
      (libsource (lib "eagle-import") (part "BTS50015-1TAD"))
    )
    (comp (ref "U14")
      (value "LTC4121")
      (footprint "eagle-import:QFN-16-PAD")
      (libsource (lib "eagle-import") (part "LTC4121"))
    )
    (comp (ref "U18")
      (value "AD8418")
      (footprint "eagle-import:MSOP-8")
      (libsource (lib "eagle-import") (part "AD8418"))
    )
    (comp (ref "V32")
      (value "LFB1_CHG")
      (footprint "eagle-import:VIA-60MIL-SQ")
      (libsource (lib "eagle-import") (part "VIA60MIL-SQ"))
    )
    (comp (ref "V35")
      (value "LFB1_CHG")
      (footprint "eagle-import:VIA-60MIL")
      (libsource (lib "eagle-import") (part "VIA-60MIL"))
    )
    (comp (ref "V40")
      (value "LFB1SNS")
      (footprint "eagle-import:VIA-60MIL")
      (libsource (lib "eagle-import") (part "VIA-60MIL"))
    )
    (comp (ref "V41")
      (value "LF1_REF")
      (footprint "eagle-import:VIA-60MIL")
      (libsource (lib "eagle-import") (part "VIA-60MIL"))
    )
    (comp (ref "V42")
      (value "LF2_REF")
      (footprint "eagle-import:VIA-60MIL")
      (libsource (lib "eagle-import") (part "VIA-60MIL"))
    )
    (comp (ref "V43")
      (value "LFB1_OUTEN")
      (footprint "eagle-import:VIA-60MIL")
      (libsource (lib "eagle-import") (part "VIA-60MIL"))
    )
    (comp (ref "V45")
      (value "LF_B1")
      (footprint "eagle-import:VIA-120MIL")
      (libsource (lib "eagle-import") (part "VIA-120MIL"))
    )
    (comp (ref "V46")
      (value "LFB1_OSNS")
      (footprint "eagle-import:VIA-60MIL")
      (libsource (lib "eagle-import") (part "VIA-60MIL"))
    )
    (comp (ref "C3")
      (value "0.1uF")
      (footprint "eagle-import:0805")
      (libsource (lib "eagle-import") (part "CAP0805"))
    )
    (comp (ref "C4")
      (value "0.1uF")
      (footprint "eagle-import:0805")
      (libsource (lib "eagle-import") (part "CAP0805"))
    )
    (comp (ref "C43")
      (value "1uF")
      (footprint "eagle-import:0805")
      (libsource (lib "eagle-import") (part "CAP0805"))
    )
    (comp (ref "D1")
      (value "DFLS130L")
      (footprint "eagle-import:PWRDI-123")
      (libsource (lib "eagle-import") (part "DFLS130L"))
    )
    (comp (ref "M1")
      (value "BSO201SP")
      (footprint "eagle-import:SO-8")
      (libsource (lib "eagle-import") (part "BSO201SP"))
    )
    (comp (ref "R13")
      (value "40K")
      (footprint "eagle-import:0805")
      (libsource (lib "eagle-import") (part "RES0805"))
    )
    (comp (ref "R14")
      (value "10K")
      (footprint "eagle-import:0805")
      (libsource (lib "eagle-import") (part "RES0805"))
    )
    (comp (ref "R83")
      (value "470K")
      (footprint "eagle-import:0805")
      (libsource (lib "eagle-import") (part "RES0805"))
    )
    (comp (ref "U3")
      (value "LTC4412MPS6")
      (footprint "eagle-import:TSOT23-6")
      (libsource (lib "eagle-import") (part "LTC4412"))
    )
    (comp (ref "V13")
      (value "X_P")
      (footprint "eagle-import:VIA-60MIL")
      (libsource (lib "eagle-import") (part "VIA-60MIL"))
    )
    (comp (ref "V14")
      (value "X_P")
      (footprint "eagle-import:VIA-60MIL-SQ")
      (libsource (lib "eagle-import") (part "VIA60MIL-SQ"))
    )
    (comp (ref "V15")
      (value "X_N")
      (footprint "eagle-import:VIA-60MIL")
      (libsource (lib "eagle-import") (part "VIA-60MIL"))
    )
    (comp (ref "V16")
      (value "Z_P")
      (footprint "eagle-import:VIA-60MIL")
      (libsource (lib "eagle-import") (part "VIA-60MIL"))
    )
    (comp (ref "V17")
      (value "Z_N")
      (footprint "eagle-import:VIA-60MIL")
      (libsource (lib "eagle-import") (part "VIA-60MIL"))
    )
    (comp (ref "V18")
      (value "Y_N")
      (footprint "eagle-import:VIA-60MIL")
      (libsource (lib "eagle-import") (part "VIA-60MIL"))
    )
    (comp (ref "V19")
      (value "UMB_CHG")
      (footprint "eagle-import:VIA-60MIL")
      (libsource (lib "eagle-import") (part "VIA-60MIL"))
    )
    (comp (ref "C15")
      (value "1uF")
      (footprint "eagle-import:0805")
      (libsource (lib "eagle-import") (part "CAP0805"))
    )
    (comp (ref "C16")
      (value "1uF")
      (footprint "eagle-import:0805")
      (libsource (lib "eagle-import") (part "CAP0805"))
    )
    (comp (ref "C17")
      (value "1uF")
      (footprint "eagle-import:0805")
      (libsource (lib "eagle-import") (part "CAP0805"))
    )
    (comp (ref "C18")
      (value "1uF")
      (footprint "eagle-import:0805")
      (libsource (lib "eagle-import") (part "CAP0805"))
    )
    (comp (ref "C19")
      (value "0.01uF")
      (footprint "eagle-import:0805")
      (libsource (lib "eagle-import") (part "CAP0805"))
    )
    (comp (ref "C20")
      (value "0.01uF")
      (footprint "eagle-import:0805")
      (libsource (lib "eagle-import") (part "CAP0805"))
    )
    (comp (ref "C21")
      (value "4.7uF")
      (footprint "eagle-import:0805")
      (libsource (lib "eagle-import") (part "CAP0805"))
    )
    (comp (ref "C22")
      (value "4.7uF")
      (footprint "eagle-import:0805")
      (libsource (lib "eagle-import") (part "CAP0805"))
    )
    (comp (ref "C23")
      (value "10uF")
      (footprint "eagle-import:0805")
      (libsource (lib "eagle-import") (part "CAP0805"))
    )
    (comp (ref "C24")
      (value "10uF")
      (footprint "eagle-import:0805")
      (libsource (lib "eagle-import") (part "CAP0805"))
    )
    (comp (ref "C42")
      (value "1uF")
      (footprint "eagle-import:0805")
      (libsource (lib "eagle-import") (part "CAP0805"))
    )
    (comp (ref "D2")
      (value "DFLS130L")
      (footprint "eagle-import:PWRDI-123")
      (libsource (lib "eagle-import") (part "DFLS130L"))
    )
    (comp (ref "D3")
      (value "DFLS130L")
      (footprint "eagle-import:PWRDI-123")
      (libsource (lib "eagle-import") (part "DFLS130L"))
    )
    (comp (ref "R5")
      (value "100K")
      (footprint "eagle-import:0805")
      (libsource (lib "eagle-import") (part "RES0805"))
    )
    (comp (ref "R37")
      (value "470K")
      (footprint "eagle-import:0805")
      (libsource (lib "eagle-import") (part "RES0805"))
    )
    (comp (ref "R38")
      (value "470K")
      (footprint "eagle-import:0805")
      (libsource (lib "eagle-import") (part "RES0805"))
    )
    (comp (ref "R39")
      (value "15K")
      (footprint "eagle-import:0805")
      (libsource (lib "eagle-import") (part "RES0805"))
    )
    (comp (ref "R40")
      (value "10K")
      (footprint "eagle-import:0805")
      (libsource (lib "eagle-import") (part "RES0805"))
    )
    (comp (ref "R54")
      (value "100K")
      (footprint "eagle-import:0805")
      (libsource (lib "eagle-import") (part "RES0805"))
    )
    (comp (ref "U10")
      (value "LT1962-3")
      (footprint "eagle-import:MSOP-8")
      (libsource (lib "eagle-import") (part "LT1962-3"))
    )
    (comp (ref "U11")
      (value "LT1962-3")
      (footprint "eagle-import:MSOP-8")
      (libsource (lib "eagle-import") (part "LT1962-3"))
    )
    (comp (ref "U12")
      (value "LTC4411")
      (footprint "eagle-import:TSOT23-5")
      (libsource (lib "eagle-import") (part "LTC4411"))
    )
    (comp (ref "U13")
      (value "LTC4411")
      (footprint "eagle-import:TSOT23-5")
      (libsource (lib "eagle-import") (part "LTC4411"))
    )
    (comp (ref "V29")
      (value "L1_DISG")
      (footprint "eagle-import:VIA-60MIL")
      (libsource (lib "eagle-import") (part "VIA-60MIL"))
    )
    (comp (ref "V30")
      (value "L2_DISG")
      (footprint "eagle-import:VIA-60MIL")
      (libsource (lib "eagle-import") (part "VIA-60MIL"))
    )
    (comp (ref "V34")
      (value "L_OUT")
      (footprint "eagle-import:VIA-120MIL")
      (libsource (lib "eagle-import") (part "VIA-120MIL"))
    )
  )
  (nets
    (net (code "1") (name "+3V3") (class "Default")
      (node (ref "C1") (pin "1") (pinfunction "P$1_1") (pintype "passive"))
      (node (ref "C2") (pin "1") (pinfunction "P$1_1") (pintype "passive"))
      (node (ref "R17") (pin "2") (pinfunction "2_2") (pintype "passive"))
      (node (ref "R18") (pin "2") (pinfunction "2_2") (pintype "passive"))
      (node (ref "R2") (pin "2") (pinfunction "2_2") (pintype "passive"))
      (node (ref "R20") (pin "1") (pinfunction "1_1") (pintype "passive"))
      (node (ref "R24") (pin "1") (pinfunction "1_1") (pintype "passive"))
      (node (ref "R29") (pin "1") (pinfunction "1_1") (pintype "passive"))
      (node (ref "R3") (pin "2") (pinfunction "2_2") (pintype "passive"))
      (node (ref "R4") (pin "1") (pinfunction "1_1") (pintype "passive"))
      (node (ref "R42") (pin "2") (pinfunction "2_2") (pintype "passive"))
      (node (ref "R43") (pin "2") (pinfunction "2_2") (pintype "passive"))
      (node (ref "R60") (pin "2") (pinfunction "2_2") (pintype "passive"))
      (node (ref "R61") (pin "2") (pinfunction "2_2") (pintype "passive"))
      (node (ref "R83") (pin "2") (pinfunction "2_2") (pintype "passive"))
      (node (ref "R84") (pin "2") (pinfunction "2_2") (pintype "passive"))
      (node (ref "R85") (pin "2") (pinfunction "2_2") (pintype "passive"))
      (node (ref "R86") (pin "2") (pinfunction "2_2") (pintype "passive"))
      (node (ref "U1") (pin "P$24") (pinfunction "VCC_P$24") (pintype "power_in"))
      (node (ref "U18") (pin "P$6") (pinfunction "VS_P$6") (pintype "bidirectional"))
      (node (ref "U19") (pin "P$6") (pinfunction "VS_P$6") (pintype "bidirectional"))
      (node (ref "U2") (pin "P$8") (pinfunction "VDD_P$8") (pintype "bidirectional"))
      (node (ref "U8") (pin "P$6") (pinfunction "VS_P$6") (pintype "bidirectional"))
      (node (ref "U9") (pin "P$6") (pinfunction "VS_P$6") (pintype "bidirectional"))
      (node (ref "V12") (pin "P$1") (pinfunction "P$1_P$1") (pintype "bidirectional"))
    )
    (net (code "2") (name "5V") (class "Default")
      (node (ref "T1") (pin "+") (pinfunction "+_+") (pintype "bidirectional"))
      (node (ref "T2") (pin "+") (pinfunction "+_+") (pintype "bidirectional"))
      (node (ref "T3") (pin "+") (pinfunction "+_+") (pintype "bidirectional"))
      (node (ref "T4") (pin "+") (pinfunction "+_+") (pintype "bidirectional"))
      (node (ref "V7") (pin "P$1") (pinfunction "P$1_P$1") (pintype "bidirectional"))
    )
    (net (code "3") (name "GND") (class "Default")
      (node (ref "C1") (pin "2") (pinfunction "P$2_2") (pintype "passive"))
      (node (ref "C11") (pin "2") (pinfunction "P$2_2") (pintype "passive"))
      (node (ref "C12") (pin "2") (pinfunction "P$2_2") (pintype "passive"))
      (node (ref "C13") (pin "1") (pinfunction "P$1_1") (pintype "passive"))
      (node (ref "C14") (pin "1") (pinfunction "P$1_1") (pintype "passive"))
      (node (ref "C15") (pin "1") (pinfunction "P$1_1") (pintype "passive"))
      (node (ref "C16") (pin "1") (pinfunction "P$1_1") (pintype "passive"))
      (node (ref "C17") (pin "2") (pinfunction "P$2_2") (pintype "passive"))
      (node (ref "C18") (pin "2") (pinfunction "P$2_2") (pintype "passive"))
      (node (ref "C2") (pin "2") (pinfunction "P$2_2") (pintype "passive"))
      (node (ref "C21") (pin "2") (pinfunction "P$2_2") (pintype "passive"))
      (node (ref "C22") (pin "2") (pinfunction "P$2_2") (pintype "passive"))
      (node (ref "C23") (pin "2") (pinfunction "P$2_2") (pintype "passive"))
      (node (ref "C24") (pin "2") (pinfunction "P$2_2") (pintype "passive"))
      (node (ref "C25") (pin "1") (pinfunction "P$1_1") (pintype "passive"))
      (node (ref "C26") (pin "1") (pinfunction "P$1_1") (pintype "passive"))
      (node (ref "C28") (pin "2") (pinfunction "P$2_2") (pintype "passive"))
      (node (ref "C29") (pin "1") (pinfunction "P$1_1") (pintype "passive"))
      (node (ref "C3") (pin "2") (pinfunction "P$2_2") (pintype "passive"))
      (node (ref "C30") (pin "2") (pinfunction "P$2_2") (pintype "passive"))
      (node (ref "C31") (pin "2") (pinfunction "P$2_2") (pintype "passive"))
      (node (ref "C32") (pin "1") (pinfunction "P$1_1") (pintype "passive"))
      (node (ref "C33") (pin "1") (pinfunction "P$1_1") (pintype "passive"))
      (node (ref "C35") (pin "2") (pinfunction "P$2_2") (pintype "passive"))
      (node (ref "C36") (pin "1") (pinfunction "P$1_1") (pintype "passive"))
      (node (ref "C37") (pin "2") (pinfunction "P$2_2") (pintype "passive"))
      (node (ref "C38") (pin "2") (pinfunction "P$2_2") (pintype "passive"))
      (node (ref "C39") (pin "1") (pinfunction "P$1_1") (pintype "passive"))
      (node (ref "C4") (pin "2") (pinfunction "P$2_2") (pintype "passive"))
      (node (ref "C40") (pin "1") (pinfunction "P$1_1") (pintype "passive"))
      (node (ref "C41") (pin "2") (pinfunction "P$2_2") (pintype "passive"))
      (node (ref "C42") (pin "2") (pinfunction "P$2_2") (pintype "passive"))
      (node (ref "C43") (pin "2") (pinfunction "P$2_2") (pintype "passive"))
      (node (ref "C44") (pin "1") (pinfunction "P$1_1") (pintype "passive"))
      (node (ref "C45") (pin "1") (pinfunction "P$1_1") (pintype "passive"))
      (node (ref "C46") (pin "1") (pinfunction "P$1_1") (pintype "passive"))
      (node (ref "C47") (pin "1") (pinfunction "P$1_1") (pintype "passive"))
      (node (ref "C48") (pin "1") (pinfunction "P$1_1") (pintype "passive"))
      (node (ref "C49") (pin "1") (pinfunction "P$1_1") (pintype "passive"))
      (node (ref "C5") (pin "2") (pinfunction "P$2_2") (pintype "passive"))
      (node (ref "C6") (pin "2") (pinfunction "P$2_2") (pintype "passive"))
      (node (ref "C7") (pin "2") (pinfunction "P$2_2") (pintype "passive"))
      (node (ref "C8") (pin "2") (pinfunction "P$2_2") (pintype "passive"))
      (node (ref "D4") (pin "A") (pinfunction "A_A") (pintype "passive"))
      (node (ref "D5") (pin "A") (pinfunction "A_A") (pintype "passive"))
      (node (ref "R11") (pin "1") (pinfunction "1_1") (pintype "passive"))
      (node (ref "R14") (pin "1") (pinfunction "1_1") (pintype "passive"))
      (node (ref "R19") (pin "1") (pinfunction "1_1") (pintype "passive"))
      (node (ref "R21") (pin "2") (pinfunction "2_2") (pintype "passive"))
      (node (ref "R23") (pin "1") (pinfunction "1_1") (pintype "passive"))
      (node (ref "R25") (pin "1") (pinfunction "1_1") (pintype "passive"))
      (node (ref "R26") (pin "2") (pinfunction "2_2") (pintype "passive"))
      (node (ref "R28") (pin "1") (pinfunction "1_1") (pintype "passive"))
      (node (ref "R30") (pin "2") (pinfunction "2_2") (pintype "passive"))
      (node (ref "R32") (pin "1") (pinfunction "1_1") (pintype "passive"))
      (node (ref "R34") (pin "1") (pinfunction "1_1") (pintype "passive"))
      (node (ref "R35") (pin "1") (pinfunction "1_1") (pintype "passive"))
      (node (ref "R36") (pin "1") (pinfunction "1_1") (pintype "passive"))
      (node (ref "R40") (pin "1") (pinfunction "1_1") (pintype "passive"))
      (node (ref "R41") (pin "P$1") (pinfunction "1_P$1") (pintype "passive"))
      (node (ref "R41") (pin "P$2") (pinfunction "1_P$2") (pintype "passive"))
      (node (ref "R44") (pin "1") (pinfunction "1_1") (pintype "passive"))
      (node (ref "R46") (pin "1") (pinfunction "1_1") (pintype "passive"))
      (node (ref "R48") (pin "1") (pinfunction "1_1") (pintype "passive"))
      (node (ref "R5") (pin "1") (pinfunction "1_1") (pintype "passive"))
      (node (ref "R50") (pin "1") (pinfunction "1_1") (pintype "passive"))
      (node (ref "R51") (pin "2") (pinfunction "2_2") (pintype "passive"))
      (node (ref "R54") (pin "1") (pinfunction "1_1") (pintype "passive"))
      (node (ref "R55") (pin "1") (pinfunction "1_1") (pintype "passive"))
      (node (ref "R56") (pin "1") (pinfunction "1_1") (pintype "passive"))
      (node (ref "R57") (pin "1") (pinfunction "1_1") (pintype "passive"))
      (node (ref "R58") (pin "1") (pinfunction "1_1") (pintype "passive"))
      (node (ref "R59") (pin "P$1") (pinfunction "1_P$1") (pintype "passive"))
      (node (ref "R59") (pin "P$2") (pinfunction "1_P$2") (pintype "passive"))
      (node (ref "R6") (pin "2") (pinfunction "2_2") (pintype "passive"))
      (node (ref "R62") (pin "1") (pinfunction "1_1") (pintype "passive"))
      (node (ref "R64") (pin "1") (pinfunction "1_1") (pintype "passive"))
      (node (ref "R66") (pin "1") (pinfunction "1_1") (pintype "passive"))
      (node (ref "R68") (pin "1") (pinfunction "1_1") (pintype "passive"))
      (node (ref "R69") (pin "2") (pinfunction "2_2") (pintype "passive"))
      (node (ref "R72") (pin "1") (pinfunction "1_1") (pintype "passive"))
      (node (ref "R76") (pin "1") (pinfunction "1_1") (pintype "passive"))
      (node (ref "R77") (pin "1") (pinfunction "1_1") (pintype "passive"))
      (node (ref "R8") (pin "1") (pinfunction "1_1") (pintype "passive"))
      (node (ref "R80") (pin "1") (pinfunction "1_1") (pintype "passive"))
      (node (ref "R9") (pin "1") (pinfunction "1_1") (pintype "passive"))
      (node (ref "SW1") (pin "P$1") (pinfunction "GND_P$1") (pintype "bidirectional"))
      (node (ref "SW2") (pin "P$1") (pinfunction "GND_P$1") (pintype "bidirectional"))
      (node (ref "U1") (pin "P$12") (pinfunction "GND_P$12") (pintype "power_in"))
      (node (ref "U1") (pin "P$2") (pinfunction "A1_P$2") (pintype "bidirectional"))
      (node (ref "U1") (pin "P$21") (pinfunction "A0_P$21") (pintype "bidirectional"))
      (node (ref "U1") (pin "P$3") (pinfunction "A2_P$3") (pintype "bidirectional"))
      (node (ref "U10") (pin "P$4") (pinfunction "GND_P$4") (pintype "bidirectional"))
      (node (ref "U10") (pin "P$6") (pinfunction "NC_P$6") (pintype "bidirectional"))
      (node (ref "U10") (pin "P$7") (pinfunction "NC_P$7") (pintype "bidirectional"))
      (node (ref "U11") (pin "P$4") (pinfunction "GND_P$4") (pintype "bidirectional"))
      (node (ref "U11") (pin "P$6") (pinfunction "NC_P$6") (pintype "bidirectional"))
      (node (ref "U11") (pin "P$7") (pinfunction "NC_P$7") (pintype "bidirectional"))
      (node (ref "U12") (pin "P$2") (pinfunction "GND_P$2") (pintype "bidirectional"))
      (node (ref "U13") (pin "P$2") (pinfunction "GND_P$2") (pintype "bidirectional"))
      (node (ref "U14") (pin "P$12") (pinfunction "NTC_P$12") (pintype "bidirectional"))
      (node (ref "U14") (pin "P$17") (pinfunction "GND_P$17") (pintype "bidirectional"))
      (node (ref "U14") (pin "P$5") (pinfunction "GND_P$5") (pintype "bidirectional"))
      (node (ref "U14") (pin "P$7") (pinfunction "FREQ_P$7") (pintype "bidirectional"))
      (node (ref "U16") (pin "P$12") (pinfunction "NTC_P$12") (pintype "bidirectional"))
      (node (ref "U16") (pin "P$17") (pinfunction "GND_P$17") (pintype "bidirectional"))
      (node (ref "U16") (pin "P$5") (pinfunction "GND_P$5") (pintype "bidirectional"))
      (node (ref "U16") (pin "P$7") (pinfunction "FREQ_P$7") (pintype "bidirectional"))
      (node (ref "U18") (pin "P$1") (pinfunction "-IN_P$1") (pintype "bidirectional"))
      (node (ref "U18") (pin "P$2") (pinfunction "GND_P$2") (pintype "bidirectional"))
      (node (ref "U18") (pin "P$4") (pinfunction "NC_P$4") (pintype "bidirectional"))
      (node (ref "U19") (pin "P$1") (pinfunction "-IN_P$1") (pintype "bidirectional"))
      (node (ref "U19") (pin "P$2") (pinfunction "GND_P$2") (pintype "bidirectional"))
      (node (ref "U19") (pin "P$4") (pinfunction "NC_P$4") (pintype "bidirectional"))
      (node (ref "U2") (pin "P$7") (pinfunction "GND_P$7") (pintype "bidirectional"))
      (node (ref "U3") (pin "P$2") (pinfunction "GND_P$2") (pintype "bidirectional"))
      (node (ref "U3") (pin "P$3") (pinfunction "CNTL_P$3") (pintype "bidirectional"))
      (node (ref "U4") (pin "P$11") (pinfunction "NC_P$11") (pintype "bidirectional"))
      (node (ref "U4") (pin "P$12") (pinfunction "NTC_P$12") (pintype "bidirectional"))
      (node (ref "U4") (pin "P$17") (pinfunction "GND_P$17") (pintype "bidirectional"))
      (node (ref "U4") (pin "P$5") (pinfunction "GND_P$5") (pintype "bidirectional"))
      (node (ref "U4") (pin "P$7") (pinfunction "FREQ_P$7") (pintype "bidirectional"))
      (node (ref "U5") (pin "P$11") (pinfunction "NC_P$11") (pintype "bidirectional"))
      (node (ref "U5") (pin "P$12") (pinfunction "NTC_P$12") (pintype "bidirectional"))
      (node (ref "U5") (pin "P$17") (pinfunction "GND_P$17") (pintype "bidirectional"))
      (node (ref "U5") (pin "P$5") (pinfunction "GND_P$5") (pintype "bidirectional"))
      (node (ref "U5") (pin "P$7") (pinfunction "FREQ_P$7") (pintype "bidirectional"))
      (node (ref "U6") (pin "P$1") (pinfunction "S2_P$1") (pintype "bidirectional"))
      (node (ref "U6") (pin "P$3") (pinfunction "TST_P$3") (pintype "bidirectional"))
      (node (ref "U6") (pin "P$4") (pinfunction "VSS_P$4") (pintype "bidirectional"))
      (node (ref "U7") (pin "P$1") (pinfunction "S2_P$1") (pintype "bidirectional"))
      (node (ref "U7") (pin "P$3") (pinfunction "TST_P$3") (pintype "bidirectional"))
      (node (ref "U7") (pin "P$4") (pinfunction "VSS_P$4") (pintype "bidirectional"))
      (node (ref "U8") (pin "P$2") (pinfunction "GND_P$2") (pintype "bidirectional"))
      (node (ref "U8") (pin "P$4") (pinfunction "NC_P$4") (pintype "bidirectional"))
      (node (ref "U9") (pin "P$2") (pinfunction "GND_P$2") (pintype "bidirectional"))
      (node (ref "U9") (pin "P$4") (pinfunction "NC_P$4") (pintype "bidirectional"))
      (node (ref "V1") (pin "P$1") (pinfunction "P$1_P$1") (pintype "bidirectional"))
      (node (ref "V2") (pin "P$1") (pinfunction "P$1_P$1") (pintype "bidirectional"))
      (node (ref "V28") (pin "P$1") (pinfunction "P$1_P$1") (pintype "bidirectional"))
      (node (ref "V3") (pin "P$1") (pinfunction "P$1_P$1") (pintype "bidirectional"))
      (node (ref "V36") (pin "P$1") (pinfunction "P$1_P$1") (pintype "bidirectional"))
      (node (ref "V4") (pin "P$1") (pinfunction "P$1_P$1") (pintype "bidirectional"))
    )
    (net (code "4") (name "L1_CHG") (class "Default")
      (node (ref "R15") (pin "2") (pinfunction "2_2") (pintype "passive"))
      (node (ref "R35") (pin "2") (pinfunction "2_2") (pintype "passive"))
      (node (ref "U4") (pin "P$16") (pinfunction "RUN_P$16") (pintype "bidirectional"))
      (node (ref "V20") (pin "P$1") (pinfunction "P$1_P$1") (pintype "bidirectional"))
      (node (ref "V48") (pin "P$1") (pinfunction "P$1_P$1") (pintype "bidirectional"))
    )
    (net (code "5") (name "L1_CHGN") (class "Default")
      (node (ref "R17") (pin "1") (pinfunction "1_1") (pintype "passive"))
      (node (ref "U1") (pin "P$8") (pinfunction "P04_P$8") (pintype "bidirectional"))
      (node (ref "U4") (pin "P$14") (pinfunction "~{CHRG}_P$14") (pintype "bidirectional"))
      (node (ref "V27") (pin "P$1") (pinfunction "P$1_P$1") (pintype "bidirectional"))
    )
    (net (code "6") (name "L1_DISG") (class "Default")
      (node (ref "R5") (pin "2") (pinfunction "2_2") (pintype "passive"))
      (node (ref "U12") (pin "P$3") (pinfunction "CNTRL_P$3") (pintype "bidirectional"))
      (node (ref "V29") (pin "P$1") (pinfunction "P$1_P$1") (pintype "bidirectional"))
    )
    (net (code "7") (name "L1_FAULTN") (class "Default")
      (node (ref "R18") (pin "1") (pinfunction "1_1") (pintype "passive"))
      (node (ref "U1") (pin "P$9") (pinfunction "P05_P$9") (pintype "bidirectional"))
      (node (ref "U4") (pin "P$15") (pinfunction "~{FAULT}_P$15") (pintype "bidirectional"))
      (node (ref "V26") (pin "P$1") (pinfunction "P$1_P$1") (pintype "bidirectional"))
    )
    (net (code "8") (name "L1_PROG") (class "Default")
      (node (ref "R25") (pin "2") (pinfunction "2_2") (pintype "passive"))
      (node (ref "U4") (pin "P$13") (pinfunction "PROG_P$13") (pintype "bidirectional"))
    )
    (net (code "9") (name "L1_REF") (class "Default")
      (node (ref "R33") (pin "1") (pinfunction "1_1") (pintype "passive"))
      (node (ref "R34") (pin "2") (pinfunction "2_2") (pintype "passive"))
      (node (ref "V21") (pin "P$1") (pinfunction "P$1_P$1") (pintype "bidirectional"))
    )
    (net (code "10") (name "L1_SNS") (class "Default")
      (node (ref "C39") (pin "2") (pinfunction "P$2_2") (pintype "passive"))
      (node (ref "U2") (pin "P$4") (pinfunction "VIN1_P$4") (pintype "bidirectional"))
      (node (ref "U8") (pin "P$5") (pinfunction "OUT_P$5") (pintype "bidirectional"))
    )
    (net (code "11") (name "L1_SNS+") (class "Default")
      (node (ref "LI-ION1") (pin "MINUS") (pinfunction "MINUS_MINUS") (pintype "power_in"))
      (node (ref "R31") (pin "P$2") (pinfunction "2_P$2") (pintype "passive"))
      (node (ref "U8") (pin "P$8") (pinfunction "+IN_P$8") (pintype "bidirectional"))
    )
    (net (code "12") (name "L1_SNS-") (class "Default")
      (node (ref "R31") (pin "P$1") (pinfunction "1_P$1") (pintype "passive"))
      (node (ref "U8") (pin "P$1") (pinfunction "-IN_P$1") (pintype "bidirectional"))
      (node (ref "V22") (pin "P$1") (pinfunction "P$1_P$1") (pintype "bidirectional"))
    )
    (net (code "13") (name "L1_ST") (class "Default")
      (node (ref "R37") (pin "1") (pinfunction "1_1") (pintype "passive"))
      (node (ref "U1") (pin "P$5") (pinfunction "P01_P$5") (pintype "bidirectional"))
      (node (ref "U12") (pin "P$4") (pinfunction "STAT_P$4") (pintype "bidirectional"))
    )
    (net (code "14") (name "L1_TEMP") (class "Default")
      (node (ref "T1") (pin "-") (pinfunction "-_-") (pintype "bidirectional"))
      (node (ref "V8") (pin "P$1") (pinfunction "P$1_P$1") (pintype "bidirectional"))
    )
    (net (code "15") (name "L2_CHG") (class "Default")
      (node (ref "R1") (pin "2") (pinfunction "2_2") (pintype "passive"))
      (node (ref "R36") (pin "2") (pinfunction "2_2") (pintype "passive"))
      (node (ref "U5") (pin "P$16") (pinfunction "RUN_P$16") (pintype "bidirectional"))
      (node (ref "V33") (pin "P$1") (pinfunction "P$1_P$1") (pintype "bidirectional"))
    )
    (net (code "16") (name "L2_CHGN") (class "Default")
      (node (ref "R2") (pin "1") (pinfunction "1_1") (pintype "passive"))
      (node (ref "U1") (pin "P$10") (pinfunction "P06_P$10") (pintype "bidirectional"))
      (node (ref "U5") (pin "P$14") (pinfunction "~{CHRG}_P$14") (pintype "bidirectional"))
    )
    (net (code "17") (name "L2_DISG") (class "Default")
      (node (ref "R54") (pin "2") (pinfunction "2_2") (pintype "passive"))
      (node (ref "U13") (pin "P$3") (pinfunction "CNTRL_P$3") (pintype "bidirectional"))
      (node (ref "V30") (pin "P$1") (pinfunction "P$1_P$1") (pintype "bidirectional"))
    )
    (net (code "18") (name "L2_FAULTN") (class "Default")
      (node (ref "R3") (pin "1") (pinfunction "1_1") (pintype "passive"))
      (node (ref "U1") (pin "P$11") (pinfunction "P07_P$11") (pintype "bidirectional"))
      (node (ref "U5") (pin "P$15") (pinfunction "~{FAULT}_P$15") (pintype "bidirectional"))
    )
    (net (code "19") (name "L2_PROG") (class "Default")
      (node (ref "R9") (pin "2") (pinfunction "2_2") (pintype "passive"))
      (node (ref "U5") (pin "P$13") (pinfunction "PROG_P$13") (pintype "bidirectional"))
    )
    (net (code "20") (name "L2_REF") (class "Default")
      (node (ref "C41") (pin "1") (pinfunction "P$1_1") (pintype "passive"))
      (node (ref "R16") (pin "1") (pinfunction "1_1") (pintype "passive"))
      (node (ref "R19") (pin "2") (pinfunction "2_2") (pintype "passive"))
      (node (ref "V31") (pin "P$1") (pinfunction "P$1_P$1") (pintype "bidirectional"))
    )
    (net (code "21") (name "L2_SNS") (class "Default")
      (node (ref "C40") (pin "2") (pinfunction "P$2_2") (pintype "passive"))
      (node (ref "U2") (pin "P$3") (pinfunction "VIN0_P$3") (pintype "bidirectional"))
      (node (ref "U9") (pin "P$5") (pinfunction "OUT_P$5") (pintype "bidirectional"))
    )
    (net (code "22") (name "L2_SNS+") (class "Default")
      (node (ref "LI-ION2") (pin "MINUS") (pinfunction "MINUS_MINUS") (pintype "power_in"))
      (node (ref "R12") (pin "P$2") (pinfunction "2_P$2") (pintype "passive"))
      (node (ref "U9") (pin "P$8") (pinfunction "+IN_P$8") (pintype "bidirectional"))
    )
    (net (code "23") (name "L2_SNS-") (class "Default")
      (node (ref "R12") (pin "P$1") (pinfunction "1_P$1") (pintype "passive"))
      (node (ref "U9") (pin "P$1") (pinfunction "-IN_P$1") (pintype "bidirectional"))
      (node (ref "V24") (pin "P$1") (pinfunction "P$1_P$1") (pintype "bidirectional"))
    )
    (net (code "24") (name "L2_ST") (class "Default")
      (node (ref "R38") (pin "1") (pinfunction "1_1") (pintype "passive"))
      (node (ref "U1") (pin "P$4") (pinfunction "P00_P$4") (pintype "bidirectional"))
      (node (ref "U13") (pin "P$4") (pinfunction "STAT_P$4") (pintype "bidirectional"))
    )
    (net (code "25") (name "L2_TEMP") (class "Default")
      (node (ref "T2") (pin "-") (pinfunction "-_-") (pintype "bidirectional"))
      (node (ref "V9") (pin "P$1") (pinfunction "P$1_P$1") (pintype "bidirectional"))
    )
    (net (code "26") (name "LF-B1-CHG-IN") (class "Default")
      (node (ref "C25") (pin "2") (pinfunction "P$2_2") (pintype "passive"))
      (node (ref "D8") (pin "C") (pinfunction "C_C") (pintype "bidirectional"))
      (node (ref "R45") (pin "2") (pinfunction "2_2") (pintype "passive"))
      (node (ref "U14") (pin "P$3") (pinfunction "IN_P$3") (pintype "bidirectional"))
    )
    (net (code "27") (name "LF-B2-CHG-IN") (class "Default")
      (node (ref "C32") (pin "2") (pinfunction "P$2_2") (pintype "passive"))
      (node (ref "D9") (pin "C") (pinfunction "C_C") (pintype "bidirectional"))
      (node (ref "R63") (pin "2") (pinfunction "2_2") (pintype "passive"))
      (node (ref "U16") (pin "P$3") (pinfunction "IN_P$3") (pintype "bidirectional"))
    )
    (net (code "28") (name "LF1_REF") (class "Default")
      (node (ref "C46") (pin "2") (pinfunction "P$2_2") (pintype "passive"))
      (node (ref "R49") (pin "2") (pinfunction "2_2") (pintype "passive"))
      (node (ref "R50") (pin "2") (pinfunction "2_2") (pintype "passive"))
      (node (ref "V41") (pin "P$1") (pinfunction "P$1_P$1") (pintype "bidirectional"))
    )
    (net (code "29") (name "LF1_TEMP") (class "Default")
      (node (ref "T3") (pin "-") (pinfunction "-_-") (pintype "bidirectional"))
      (node (ref "V10") (pin "P$1") (pinfunction "P$1_P$1") (pintype "bidirectional"))
    )
    (net (code "30") (name "LF2_REF") (class "Default")
      (node (ref "C45") (pin "2") (pinfunction "P$2_2") (pintype "passive"))
      (node (ref "R47") (pin "1") (pinfunction "1_1") (pintype "passive"))
      (node (ref "R48") (pin "2") (pinfunction "2_2") (pintype "passive"))
      (node (ref "V42") (pin "P$1") (pinfunction "P$1_P$1") (pintype "bidirectional"))
    )
    (net (code "31") (name "LF3_REF") (class "Default")
      (node (ref "C47") (pin "2") (pinfunction "P$2_2") (pintype "passive"))
      (node (ref "R67") (pin "2") (pinfunction "2_2") (pintype "passive"))
      (node (ref "R68") (pin "2") (pinfunction "2_2") (pintype "passive"))
      (node (ref "V49") (pin "P$1") (pinfunction "P$1_P$1") (pintype "bidirectional"))
    )
    (net (code "32") (name "LF3_TEMP") (class "Default")
      (node (ref "T4") (pin "-") (pinfunction "-_-") (pintype "bidirectional"))
      (node (ref "V11") (pin "P$1") (pinfunction "P$1_P$1") (pintype "bidirectional"))
    )
    (net (code "33") (name "LF4_REF") (class "Default")
      (node (ref "C48") (pin "2") (pinfunction "P$2_2") (pintype "passive"))
      (node (ref "R65") (pin "1") (pinfunction "1_1") (pintype "passive"))
      (node (ref "R66") (pin "2") (pinfunction "2_2") (pintype "passive"))
      (node (ref "V50") (pin "P$1") (pinfunction "P$1_P$1") (pintype "bidirectional"))
    )
    (net (code "34") (name "LFB1_SNS+") (class "Default")
      (node (ref "LIFEPO42") (pin "MINUS") (pinfunction "MINUS_MINUS") (pintype "power_in"))
      (node (ref "R41") (pin "P$3") (pinfunction "2_P$3") (pintype "passive"))
      (node (ref "R41") (pin "P$4") (pinfunction "2_P$4") (pintype "passive"))
      (node (ref "U18") (pin "P$8") (pinfunction "+IN_P$8") (pintype "bidirectional"))
    )
    (net (code "35") (name "LFB2_SNS+") (class "Default")
      (node (ref "LIFEPO44") (pin "MINUS") (pinfunction "MINUS_MINUS") (pintype "power_in"))
      (node (ref "R59") (pin "P$3") (pinfunction "2_P$3") (pintype "passive"))
      (node (ref "R59") (pin "P$4") (pinfunction "2_P$4") (pintype "passive"))
      (node (ref "U19") (pin "P$8") (pinfunction "+IN_P$8") (pintype "bidirectional"))
    )
    (net (code "36") (name "LF_B1") (class "Default")
      (node (ref "C30") (pin "1") (pinfunction "P$1_1") (pintype "passive"))
      (node (ref "SW1") (pin "P$5") (pinfunction "OUT_P$5") (pintype "power_in"))
      (node (ref "SW1") (pin "P$6") (pinfunction "OUT_P$6") (pintype "power_in"))
      (node (ref "SW1") (pin "P$7") (pinfunction "OUT_P$7") (pintype "power_in"))
      (node (ref "V45") (pin "P$1") (pinfunction "P$1_P$1") (pintype "bidirectional"))
    )
    (net (code "38") (name "LF_B1_CHG") (class "Default")
      (node (ref "R44") (pin "2") (pinfunction "2_2") (pintype "passive"))
      (node (ref "U14") (pin "P$16") (pinfunction "RUN_P$16") (pintype "bidirectional"))
      (node (ref "V32") (pin "P$1") (pinfunction "P$1_P$1") (pintype "bidirectional"))
      (node (ref "V35") (pin "P$1") (pinfunction "P$1_P$1") (pintype "bidirectional"))
    )
    (net (code "39") (name "LF_B1_CHGN") (class "Default")
      (node (ref "R42") (pin "1") (pinfunction "1_1") (pintype "passive"))
      (node (ref "U1") (pin "P$20") (pinfunction "P17_P$20") (pintype "bidirectional"))
      (node (ref "U14") (pin "P$14") (pinfunction "~{CHRG}_P$14") (pintype "bidirectional"))
    )
    (net (code "40") (name "LF_B1_FAULTN") (class "Default")
      (node (ref "R43") (pin "1") (pinfunction "1_1") (pintype "passive"))
      (node (ref "U1") (pin "P$19") (pinfunction "P16_P$19") (pintype "bidirectional"))
      (node (ref "U14") (pin "P$15") (pinfunction "~{FAULT}_P$15") (pintype "bidirectional"))
    )
    (net (code "41") (name "LF_B1_OSNS") (class "Default")
      (node (ref "C31") (pin "1") (pinfunction "P$1_1") (pintype "passive"))
      (node (ref "R79") (pin "1") (pinfunction "1_1") (pintype "passive"))
      (node (ref "V46") (pin "P$1") (pinfunction "P$1_P$1") (pintype "bidirectional"))
    )
    (net (code "42") (name "LF_B1_OUTEN") (class "Default")
      (node (ref "R78") (pin "1") (pinfunction "1_1") (pintype "passive"))
      (node (ref "V43") (pin "P$1") (pinfunction "P$1_P$1") (pintype "bidirectional"))
    )
    (net (code "43") (name "LF_B1_SNS") (class "Default")
      (node (ref "C44") (pin "2") (pinfunction "P$2_2") (pintype "passive"))
      (node (ref "U18") (pin "P$5") (pinfunction "OUT_P$5") (pintype "bidirectional"))
      (node (ref "V40") (pin "P$1") (pinfunction "P$1_P$1") (pintype "bidirectional"))
    )
    (net (code "45") (name "LF_B2") (class "Default")
      (node (ref "C37") (pin "1") (pinfunction "P$1_1") (pintype "passive"))
      (node (ref "SW2") (pin "P$5") (pinfunction "OUT_P$5") (pintype "power_in"))
      (node (ref "SW2") (pin "P$6") (pinfunction "OUT_P$6") (pintype "power_in"))
      (node (ref "SW2") (pin "P$7") (pinfunction "OUT_P$7") (pintype "power_in"))
      (node (ref "V53") (pin "P$1") (pinfunction "P$1_P$1") (pintype "bidirectional"))
    )
    (net (code "47") (name "LF_B2_CHG") (class "Default")
      (node (ref "R62") (pin "2") (pinfunction "2_2") (pintype "passive"))
      (node (ref "U16") (pin "P$16") (pinfunction "RUN_P$16") (pintype "bidirectional"))
      (node (ref "V47") (pin "P$1") (pinfunction "P$1_P$1") (pintype "bidirectional"))
    )
    (net (code "48") (name "LF_B2_CHGN") (class "Default")
      (node (ref "R60") (pin "1") (pinfunction "1_1") (pintype "passive"))
      (node (ref "U1") (pin "P$17") (pinfunction "P14_P$17") (pintype "bidirectional"))
      (node (ref "U16") (pin "P$14") (pinfunction "~{CHRG}_P$14") (pintype "bidirectional"))
    )
    (net (code "49") (name "LF_B2_FAULTN") (class "Default")
      (node (ref "R61") (pin "1") (pinfunction "1_1") (pintype "passive"))
      (node (ref "U1") (pin "P$18") (pinfunction "P15_P$18") (pintype "bidirectional"))
      (node (ref "U16") (pin "P$15") (pinfunction "~{FAULT}_P$15") (pintype "bidirectional"))
    )
    (net (code "50") (name "LF_B2_OSNS") (class "Default")
      (node (ref "C38") (pin "1") (pinfunction "P$1_1") (pintype "passive"))
      (node (ref "R82") (pin "1") (pinfunction "1_1") (pintype "passive"))
      (node (ref "V99") (pin "P$1") (pinfunction "P$1_P$1") (pintype "bidirectional"))
    )
    (net (code "51") (name "LF_B2_OUTEN") (class "Default")
      (node (ref "R81") (pin "1") (pinfunction "1_1") (pintype "passive"))
      (node (ref "V51") (pin "P$1") (pinfunction "P$1_P$1") (pintype "bidirectional"))
    )
    (net (code "52") (name "LF_B2_SNS") (class "Default")
      (node (ref "C49") (pin "2") (pinfunction "P$2_2") (pintype "passive"))
      (node (ref "U19") (pin "P$5") (pinfunction "OUT_P$5") (pintype "bidirectional"))
      (node (ref "V44") (pin "P$1") (pinfunction "P$1_P$1") (pintype "bidirectional"))
    )
    (net (code "54") (name "LIFE1") (class "Default")
      (node (ref "C28") (pin "1") (pinfunction "P$1_1") (pintype "passive"))
      (node (ref "D4") (pin "C") (pinfunction "C_C") (pintype "passive"))
      (node (ref "F3") (pin "P$1") (pinfunction "P$1_P$1") (pintype "passive"))
      (node (ref "F4") (pin "P$1") (pinfunction "P$1_P$1") (pintype "passive"))
      (node (ref "LIFEPO41") (pin "PLUS") (pinfunction "PLUS_PLUS") (pintype "power_in"))
      (node (ref "R49") (pin "1") (pinfunction "1_1") (pintype "passive"))
      (node (ref "R53") (pin "2") (pinfunction "2_2") (pintype "passive"))
      (node (ref "U14") (pin "P$9") (pinfunction "BAT_P$9") (pintype "bidirectional"))
    )
    (net (code "55") (name "LIFE1FUSEOUT") (class "Default")
      (node (ref "F3") (pin "P$2") (pinfunction "P$2_P$2") (pintype "passive"))
      (node (ref "F4") (pin "P$2") (pinfunction "P$2_P$2") (pintype "passive"))
      (node (ref "SW1") (pin "PAD") (pinfunction "VB_PAD") (pintype "power_in"))
    )
    (net (code "56") (name "LIFE3") (class "Default")
      (node (ref "C35") (pin "1") (pinfunction "P$1_1") (pintype "passive"))
      (node (ref "D5") (pin "C") (pinfunction "C_C") (pintype "passive"))
      (node (ref "F5") (pin "P$1") (pinfunction "P$1_P$1") (pintype "passive"))
      (node (ref "F6") (pin "P$1") (pinfunction "P$1_P$1") (pintype "passive"))
      (node (ref "LIFEPO43") (pin "PLUS") (pinfunction "PLUS_PLUS") (pintype "power_in"))
      (node (ref "R67") (pin "1") (pinfunction "1_1") (pintype "passive"))
      (node (ref "R71") (pin "2") (pinfunction "2_2") (pintype "passive"))
      (node (ref "U16") (pin "P$9") (pinfunction "BAT_P$9") (pintype "bidirectional"))
    )
    (net (code "57") (name "LIFE3FUSEOUT") (class "Default")
      (node (ref "F5") (pin "P$2") (pinfunction "P$2_P$2") (pintype "passive"))
      (node (ref "F6") (pin "P$2") (pinfunction "P$2_P$2") (pintype "passive"))
      (node (ref "SW2") (pin "PAD") (pinfunction "VB_PAD") (pintype "power_in"))
    )
    (net (code "58") (name "LION1") (class "Default")
      (node (ref "C11") (pin "1") (pinfunction "P$1_1") (pintype "passive"))
      (node (ref "F1") (pin "1") (pinfunction "P$1_1") (pintype "passive"))
      (node (ref "LI-ION1") (pin "PLUS") (pinfunction "PLUS_PLUS") (pintype "power_in"))
      (node (ref "R33") (pin "2") (pinfunction "2_2") (pintype "passive"))
      (node (ref "R7") (pin "2") (pinfunction "2_2") (pintype "passive"))
      (node (ref "U4") (pin "P$10") (pinfunction "BATSNS_P$10") (pintype "bidirectional"))
      (node (ref "U4") (pin "P$9") (pinfunction "BAT_P$9") (pintype "bidirectional"))
    )
    (net (code "59") (name "LION1-CHG-IN") (class "Default")
      (node (ref "C5") (pin "1") (pinfunction "P$1_1") (pintype "passive"))
      (node (ref "D6") (pin "C") (pinfunction "C_C") (pintype "bidirectional"))
      (node (ref "R15") (pin "1") (pinfunction "1_1") (pintype "passive"))
      (node (ref "R27") (pin "2") (pinfunction "2_2") (pintype "passive"))
      (node (ref "U4") (pin "P$3") (pinfunction "IN_P$3") (pintype "bidirectional"))
    )
    (net (code "60") (name "LION1_OUT") (class "Default")
      (node (ref "C15") (pin "2") (pinfunction "P$2_2") (pintype "passive"))
      (node (ref "F1") (pin "2") (pinfunction "P$2_2") (pintype "passive"))
      (node (ref "U12") (pin "P$1") (pinfunction "IN_P$1") (pintype "bidirectional"))
    )
    (net (code "61") (name "LION2") (class "Default")
      (node (ref "C12") (pin "1") (pinfunction "P$1_1") (pintype "passive"))
      (node (ref "F2") (pin "1") (pinfunction "P$1_1") (pintype "passive"))
      (node (ref "LI-ION2") (pin "PLUS") (pinfunction "PLUS_PLUS") (pintype "power_in"))
      (node (ref "R16") (pin "2") (pinfunction "2_2") (pintype "passive"))
      (node (ref "R22") (pin "2") (pinfunction "2_2") (pintype "passive"))
      (node (ref "U5") (pin "P$10") (pinfunction "BATSNS_P$10") (pintype "bidirectional"))
      (node (ref "U5") (pin "P$9") (pinfunction "BAT_P$9") (pintype "bidirectional"))
    )
    (net (code "62") (name "LION2_OUT") (class "Default")
      (node (ref "C16") (pin "2") (pinfunction "P$2_2") (pintype "passive"))
      (node (ref "F2") (pin "2") (pinfunction "P$2_2") (pintype "passive"))
      (node (ref "U13") (pin "P$1") (pinfunction "IN_P$1") (pintype "bidirectional"))
    )
    (net (code "63") (name "L_OUT") (class "Default")
      (node (ref "C21") (pin "1") (pinfunction "P$1_1") (pintype "passive"))
      (node (ref "C22") (pin "1") (pinfunction "P$1_1") (pintype "passive"))
      (node (ref "D2") (pin "C") (pinfunction "C_C") (pintype "bidirectional"))
      (node (ref "D3") (pin "C") (pinfunction "C_C") (pintype "bidirectional"))
      (node (ref "R37") (pin "2") (pinfunction "2_2") (pintype "passive"))
      (node (ref "R38") (pin "2") (pinfunction "2_2") (pintype "passive"))
      (node (ref "R39") (pin "2") (pinfunction "2_2") (pintype "passive"))
      (node (ref "U12") (pin "P$5") (pinfunction "OUT_P$5") (pintype "bidirectional"))
      (node (ref "U13") (pin "P$5") (pinfunction "OUT_P$5") (pintype "bidirectional"))
      (node (ref "V34") (pin "P$1") (pinfunction "P$1_P$1") (pintype "bidirectional"))
    )
    (net (code "64") (name "L_REF") (class "Default")
      (node (ref "C42") (pin "1") (pinfunction "P$1_1") (pintype "passive"))
      (node (ref "R39") (pin "1") (pinfunction "1_1") (pintype "passive"))
      (node (ref "R40") (pin "2") (pinfunction "2_2") (pintype "passive"))
      (node (ref "U2") (pin "P$5") (pinfunction "VIN2_P$5") (pintype "bidirectional"))
    )
    (net (code "65") (name "Net-(C6-P$1)") (class "Default")
      (node (ref "C6") (pin "1") (pinfunction "P$1_1") (pintype "passive"))
      (node (ref "D7") (pin "C") (pinfunction "C_C") (pintype "bidirectional"))
      (node (ref "R1") (pin "1") (pinfunction "1_1") (pintype "passive"))
      (node (ref "R10") (pin "2") (pinfunction "2_2") (pintype "passive"))
      (node (ref "U5") (pin "P$3") (pinfunction "IN_P$3") (pintype "bidirectional"))
    )
    (net (code "66") (name "Net-(C7-P$1)") (class "Default")
      (node (ref "C7") (pin "1") (pinfunction "P$1_1") (pintype "passive"))
      (node (ref "U4") (pin "P$1") (pinfunction "INTVCC_P$1") (pintype "bidirectional"))
    )
    (net (code "67") (name "Net-(C8-P$1)") (class "Default")
      (node (ref "C8") (pin "1") (pinfunction "P$1_1") (pintype "passive"))
      (node (ref "U5") (pin "P$1") (pinfunction "INTVCC_P$1") (pintype "bidirectional"))
    )
    (net (code "68") (name "Net-(C9-P$1)") (class "Default")
      (node (ref "C9") (pin "1") (pinfunction "P$1_1") (pintype "passive"))
      (node (ref "U4") (pin "P$2") (pinfunction "BOOST_P$2") (pintype "bidirectional"))
    )
    (net (code "69") (name "Net-(C9-P$2)") (class "Default")
      (node (ref "C9") (pin "2") (pinfunction "P$2_2") (pintype "passive"))
      (node (ref "L1") (pin "P$1") (pinfunction "P$1_P$1") (pintype "passive"))
      (node (ref "U4") (pin "P$4") (pinfunction "SW_P$4") (pintype "bidirectional"))
    )
    (net (code "70") (name "Net-(C10-P$1)") (class "Default")
      (node (ref "C10") (pin "1") (pinfunction "P$1_1") (pintype "passive"))
      (node (ref "U5") (pin "P$2") (pinfunction "BOOST_P$2") (pintype "bidirectional"))
    )
    (net (code "71") (name "Net-(C10-P$2)") (class "Default")
      (node (ref "C10") (pin "2") (pinfunction "P$2_2") (pintype "passive"))
      (node (ref "L2") (pin "P$1") (pinfunction "P$1_P$1") (pintype "passive"))
      (node (ref "U5") (pin "P$4") (pinfunction "SW_P$4") (pintype "bidirectional"))
    )
    (net (code "72") (name "Net-(C13-P$2)") (class "Default")
      (node (ref "C13") (pin "2") (pinfunction "P$2_2") (pintype "passive"))
      (node (ref "R7") (pin "1") (pinfunction "1_1") (pintype "passive"))
      (node (ref "U6") (pin "P$5") (pinfunction "VCC_P$5") (pintype "bidirectional"))
    )
    (net (code "73") (name "Net-(C14-P$2)") (class "Default")
      (node (ref "C14") (pin "2") (pinfunction "P$2_2") (pintype "passive"))
      (node (ref "R22") (pin "1") (pinfunction "1_1") (pintype "passive"))
      (node (ref "U7") (pin "P$5") (pinfunction "VCC_P$5") (pintype "bidirectional"))
    )
    (net (code "74") (name "Net-(C19-P$1)") (class "Default")
      (node (ref "C19") (pin "1") (pinfunction "P$1_1") (pintype "passive"))
      (node (ref "C23") (pin "1") (pinfunction "P$1_1") (pintype "passive"))
      (node (ref "D2") (pin "A") (pinfunction "A_A") (pintype "bidirectional"))
      (node (ref "U10") (pin "P$1") (pinfunction "OUT_P$1") (pintype "bidirectional"))
      (node (ref "U10") (pin "P$2") (pinfunction "SENSE_P$2") (pintype "bidirectional"))
    )
    (net (code "75") (name "Net-(C19-P$2)") (class "Default")
      (node (ref "C19") (pin "2") (pinfunction "P$2_2") (pintype "passive"))
      (node (ref "U10") (pin "P$3") (pinfunction "BYP_P$3") (pintype "bidirectional"))
    )
    (net (code "76") (name "Net-(C20-P$1)") (class "Default")
      (node (ref "C20") (pin "1") (pinfunction "P$1_1") (pintype "passive"))
      (node (ref "C24") (pin "1") (pinfunction "P$1_1") (pintype "passive"))
      (node (ref "D3") (pin "A") (pinfunction "A_A") (pintype "bidirectional"))
      (node (ref "U11") (pin "P$1") (pinfunction "OUT_P$1") (pintype "bidirectional"))
      (node (ref "U11") (pin "P$2") (pinfunction "SENSE_P$2") (pintype "bidirectional"))
    )
    (net (code "77") (name "Net-(C20-P$2)") (class "Default")
      (node (ref "C20") (pin "2") (pinfunction "P$2_2") (pintype "passive"))
      (node (ref "U11") (pin "P$3") (pinfunction "BYP_P$3") (pintype "bidirectional"))
    )
    (net (code "78") (name "Net-(C26-P$2)") (class "Default")
      (node (ref "C26") (pin "2") (pinfunction "P$2_2") (pintype "passive"))
      (node (ref "U14") (pin "P$1") (pinfunction "INTVCC_P$1") (pintype "bidirectional"))
    )
    (net (code "79") (name "Net-(C27-P$1)") (class "Default")
      (node (ref "C27") (pin "1") (pinfunction "P$1_1") (pintype "passive"))
      (node (ref "L3") (pin "P$2") (pinfunction "P$2_P$2") (pintype "passive"))
      (node (ref "U14") (pin "P$4") (pinfunction "SW_P$4") (pintype "bidirectional"))
    )
    (net (code "80") (name "Net-(C27-P$2)") (class "Default")
      (node (ref "C27") (pin "2") (pinfunction "P$2_2") (pintype "passive"))
      (node (ref "U14") (pin "P$2") (pinfunction "BOOST_P$2") (pintype "bidirectional"))
    )
    (net (code "81") (name "Net-(C29-P$2)") (class "Default")
      (node (ref "C29") (pin "2") (pinfunction "P$2_2") (pintype "passive"))
      (node (ref "R77") (pin "2") (pinfunction "2_2") (pintype "passive"))
      (node (ref "R78") (pin "2") (pinfunction "2_2") (pintype "passive"))
      (node (ref "SW1") (pin "P$2") (pinfunction "CNTRL_P$2") (pintype "input"))
    )
    (net (code "82") (name "Net-(C33-P$2)") (class "Default")
      (node (ref "C33") (pin "2") (pinfunction "P$2_2") (pintype "passive"))
      (node (ref "U16") (pin "P$1") (pinfunction "INTVCC_P$1") (pintype "bidirectional"))
    )
    (net (code "83") (name "Net-(C34-P$1)") (class "Default")
      (node (ref "C34") (pin "1") (pinfunction "P$1_1") (pintype "passive"))
      (node (ref "L4") (pin "P$2") (pinfunction "P$2_P$2") (pintype "passive"))
      (node (ref "U16") (pin "P$4") (pinfunction "SW_P$4") (pintype "bidirectional"))
    )
    (net (code "84") (name "Net-(C34-P$2)") (class "Default")
      (node (ref "C34") (pin "2") (pinfunction "P$2_2") (pintype "passive"))
      (node (ref "U16") (pin "P$2") (pinfunction "BOOST_P$2") (pintype "bidirectional"))
    )
    (net (code "85") (name "Net-(C36-P$2)") (class "Default")
      (node (ref "C36") (pin "2") (pinfunction "P$2_2") (pintype "passive"))
      (node (ref "R80") (pin "2") (pinfunction "2_2") (pintype "passive"))
      (node (ref "R81") (pin "2") (pinfunction "2_2") (pintype "passive"))
      (node (ref "SW2") (pin "P$2") (pinfunction "CNTRL_P$2") (pintype "input"))
    )
    (net (code "86") (name "Net-(LIFEPO41-PadMINUS)") (class "Default")
      (node (ref "LIFEPO41") (pin "MINUS") (pinfunction "MINUS_MINUS") (pintype "power_in"))
      (node (ref "LIFEPO42") (pin "PLUS") (pinfunction "PLUS_PLUS") (pintype "power_in"))
      (node (ref "R47") (pin "2") (pinfunction "2_2") (pintype "passive"))
    )
    (net (code "87") (name "Net-(LIFEPO43-PadMINUS)") (class "Default")
      (node (ref "LIFEPO43") (pin "MINUS") (pinfunction "MINUS_MINUS") (pintype "power_in"))
      (node (ref "LIFEPO44") (pin "PLUS") (pinfunction "PLUS_PLUS") (pintype "power_in"))
      (node (ref "R65") (pin "2") (pinfunction "2_2") (pintype "passive"))
    )
    (net (code "88") (name "Net-(M1-G)") (class "Default")
      (node (ref "M1") (pin "P$4") (pinfunction "G_P$4") (pintype "bidirectional"))
      (node (ref "U3") (pin "P$5") (pinfunction "GATE_P$5") (pintype "bidirectional"))
    )
    (net (code "89") (name "Net-(SW1-ISNS)") (class "Default")
      (node (ref "R58") (pin "2") (pinfunction "2_2") (pintype "passive"))
      (node (ref "R79") (pin "2") (pinfunction "2_2") (pintype "passive"))
      (node (ref "SW1") (pin "P$3") (pinfunction "ISNS_P$3") (pintype "output"))
    )
    (net (code "90") (name "Net-(SW2-ISNS)") (class "Default")
      (node (ref "R76") (pin "2") (pinfunction "2_2") (pintype "passive"))
      (node (ref "R82") (pin "2") (pinfunction "2_2") (pintype "passive"))
      (node (ref "SW2") (pin "P$3") (pinfunction "ISNS_P$3") (pintype "output"))
    )
    (net (code "91") (name "Net-(U1-P03)") (class "Default")
      (node (ref "R32") (pin "2") (pinfunction "2_2") (pintype "passive"))
      (node (ref "U1") (pin "P$7") (pinfunction "P03_P$7") (pintype "bidirectional"))
    )
    (net (code "92") (name "Net-(U1-P10)") (class "Default")
      (node (ref "R72") (pin "2") (pinfunction "2_2") (pintype "passive"))
      (node (ref "U1") (pin "P$13") (pinfunction "P10_P$13") (pintype "bidirectional"))
    )
    (net (code "93") (name "Net-(U1-P11)") (class "Default")
      (node (ref "R57") (pin "2") (pinfunction "2_2") (pintype "passive"))
      (node (ref "U1") (pin "P$14") (pinfunction "P11_P$14") (pintype "bidirectional"))
    )
    (net (code "94") (name "Net-(U1-P12)") (class "Default")
      (node (ref "R56") (pin "2") (pinfunction "2_2") (pintype "passive"))
      (node (ref "U1") (pin "P$15") (pinfunction "P12_P$15") (pintype "bidirectional"))
    )
    (net (code "95") (name "Net-(U1-P13)") (class "Default")
      (node (ref "R55") (pin "2") (pinfunction "2_2") (pintype "passive"))
      (node (ref "U1") (pin "P$16") (pinfunction "P13_P$16") (pintype "bidirectional"))
    )
    (net (code "96") (name "Net-(U4-CHGSNS)") (class "Default")
      (node (ref "L1") (pin "P$2") (pinfunction "P$2_P$2") (pintype "passive"))
      (node (ref "U4") (pin "P$8") (pinfunction "CHGSNS_P$8") (pintype "bidirectional"))
    )
    (net (code "97") (name "Net-(U4-MPPT)") (class "Default")
      (node (ref "R27") (pin "1") (pinfunction "1_1") (pintype "passive"))
      (node (ref "R28") (pin "2") (pinfunction "2_2") (pintype "passive"))
      (node (ref "U4") (pin "P$6") (pinfunction "MPPT_P$6") (pintype "bidirectional"))
    )
    (net (code "98") (name "Net-(U5-CHGSNS)") (class "Default")
      (node (ref "L2") (pin "P$2") (pinfunction "P$2_P$2") (pintype "passive"))
      (node (ref "U5") (pin "P$8") (pinfunction "CHGSNS_P$8") (pintype "bidirectional"))
    )
    (net (code "99") (name "Net-(U5-MPPT)") (class "Default")
      (node (ref "R10") (pin "1") (pinfunction "1_1") (pintype "passive"))
      (node (ref "R11") (pin "2") (pinfunction "2_2") (pintype "passive"))
      (node (ref "U5") (pin "P$6") (pinfunction "MPPT_P$6") (pintype "bidirectional"))
    )
    (net (code "100") (name "Net-(U6-CS)") (class "Default")
      (node (ref "R8") (pin "2") (pinfunction "2_2") (pintype "passive"))
      (node (ref "U6") (pin "P$2") (pinfunction "CS_P$2") (pintype "bidirectional"))
    )
    (net (code "101") (name "Net-(U6-S1)") (class "Default")
      (node (ref "U6") (pin "P$6") (pinfunction "S1_P$6") (pintype "bidirectional"))
      (node (ref "V23") (pin "P$1") (pinfunction "P$1_P$1") (pintype "bidirectional"))
    )
    (net (code "102") (name "Net-(U7-CS)") (class "Default")
      (node (ref "R23") (pin "2") (pinfunction "2_2") (pintype "passive"))
      (node (ref "U7") (pin "P$2") (pinfunction "CS_P$2") (pintype "bidirectional"))
    )
    (net (code "103") (name "Net-(U7-S1)") (class "Default")
      (node (ref "U7") (pin "P$6") (pinfunction "S1_P$6") (pintype "bidirectional"))
      (node (ref "V25") (pin "P$1") (pinfunction "P$1_P$1") (pintype "bidirectional"))
    )
    (net (code "104") (name "Net-(U8-VREF1)") (class "Default")
      (node (ref "R4") (pin "2") (pinfunction "2_2") (pintype "passive"))
      (node (ref "R6") (pin "1") (pinfunction "1_1") (pintype "passive"))
      (node (ref "U8") (pin "P$3") (pinfunction "VREF2_P$3") (pintype "bidirectional"))
      (node (ref "U8") (pin "P$7") (pinfunction "VREF1_P$7") (pintype "bidirectional"))
    )
    (net (code "105") (name "Net-(U9-VREF1)") (class "Default")
      (node (ref "R20") (pin "2") (pinfunction "2_2") (pintype "passive"))
      (node (ref "R21") (pin "1") (pinfunction "1_1") (pintype "passive"))
      (node (ref "U9") (pin "P$3") (pinfunction "VREF2_P$3") (pintype "bidirectional"))
      (node (ref "U9") (pin "P$7") (pinfunction "VREF1_P$7") (pintype "bidirectional"))
    )
    (net (code "106") (name "Net-(U14-CHGSNS)") (class "Default")
      (node (ref "L3") (pin "P$1") (pinfunction "P$1_P$1") (pintype "passive"))
      (node (ref "U14") (pin "P$8") (pinfunction "CHGSNS_P$8") (pintype "bidirectional"))
    )
    (net (code "107") (name "Net-(U14-FB)") (class "Default")
      (node (ref "R52") (pin "2") (pinfunction "2_2") (pintype "passive"))
      (node (ref "R53") (pin "1") (pinfunction "1_1") (pintype "passive"))
      (node (ref "U14") (pin "P$10") (pinfunction "FB_P$10") (pintype "bidirectional"))
    )
    (net (code "108") (name "Net-(U14-FBG)") (class "Default")
      (node (ref "R52") (pin "1") (pinfunction "1_1") (pintype "passive"))
      (node (ref "U14") (pin "P$11") (pinfunction "FBG_P$11") (pintype "bidirectional"))
    )
    (net (code "109") (name "Net-(U14-MPPT)") (class "Default")
      (node (ref "R45") (pin "1") (pinfunction "1_1") (pintype "passive"))
      (node (ref "R46") (pin "2") (pinfunction "2_2") (pintype "passive"))
      (node (ref "U14") (pin "P$6") (pinfunction "MPPT_P$6") (pintype "bidirectional"))
    )
    (net (code "110") (name "Net-(U14-PROG)") (class "Default")
      (node (ref "R51") (pin "1") (pinfunction "1_1") (pintype "passive"))
      (node (ref "U14") (pin "P$13") (pinfunction "PROG_P$13") (pintype "bidirectional"))
    )
    (net (code "111") (name "Net-(U16-CHGSNS)") (class "Default")
      (node (ref "L4") (pin "P$1") (pinfunction "P$1_P$1") (pintype "passive"))
      (node (ref "U16") (pin "P$8") (pinfunction "CHGSNS_P$8") (pintype "bidirectional"))
    )
    (net (code "112") (name "Net-(U16-FB)") (class "Default")
      (node (ref "R70") (pin "2") (pinfunction "2_2") (pintype "passive"))
      (node (ref "R71") (pin "1") (pinfunction "1_1") (pintype "passive"))
      (node (ref "U16") (pin "P$10") (pinfunction "FB_P$10") (pintype "bidirectional"))
    )
    (net (code "113") (name "Net-(U16-FBG)") (class "Default")
      (node (ref "R70") (pin "1") (pinfunction "1_1") (pintype "passive"))
      (node (ref "U16") (pin "P$11") (pinfunction "FBG_P$11") (pintype "bidirectional"))
    )
    (net (code "114") (name "Net-(U16-MPPT)") (class "Default")
      (node (ref "R63") (pin "1") (pinfunction "1_1") (pintype "passive"))
      (node (ref "R64") (pin "2") (pinfunction "2_2") (pintype "passive"))
      (node (ref "U16") (pin "P$6") (pinfunction "MPPT_P$6") (pintype "bidirectional"))
    )
    (net (code "115") (name "Net-(U16-PROG)") (class "Default")
      (node (ref "R69") (pin "1") (pinfunction "1_1") (pintype "passive"))
      (node (ref "U16") (pin "P$13") (pinfunction "PROG_P$13") (pintype "bidirectional"))
    )
    (net (code "116") (name "Net-(U18-VREF1)") (class "Default")
      (node (ref "R24") (pin "2") (pinfunction "2_2") (pintype "passive"))
      (node (ref "R26") (pin "1") (pinfunction "1_1") (pintype "passive"))
      (node (ref "U18") (pin "P$3") (pinfunction "VREF2_P$3") (pintype "bidirectional"))
      (node (ref "U18") (pin "P$7") (pinfunction "VREF1_P$7") (pintype "bidirectional"))
    )
    (net (code "117") (name "Net-(U19-VREF1)") (class "Default")
      (node (ref "R29") (pin "2") (pinfunction "2_2") (pintype "passive"))
      (node (ref "R30") (pin "1") (pinfunction "1_1") (pintype "passive"))
      (node (ref "U19") (pin "P$3") (pinfunction "VREF2_P$3") (pintype "bidirectional"))
      (node (ref "U19") (pin "P$7") (pinfunction "VREF1_P$7") (pintype "bidirectional"))
    )
    (net (code "118") (name "PANELREF") (class "Default")
      (node (ref "C43") (pin "1") (pinfunction "P$1_1") (pintype "passive"))
      (node (ref "R13") (pin "1") (pinfunction "1_1") (pintype "passive"))
      (node (ref "R14") (pin "2") (pinfunction "2_2") (pintype "passive"))
      (node (ref "U2") (pin "P$6") (pinfunction "VIN3/REF_P$6") (pintype "bidirectional"))
    )
    (net (code "119") (name "SCL") (class "Default")
      (node (ref "R85") (pin "1") (pinfunction "1_1") (pintype "passive"))
      (node (ref "U1") (pin "P$22") (pinfunction "SCL_P$22") (pintype "bidirectional"))
      (node (ref "U2") (pin "P$1") (pinfunction "SCL_P$1") (pintype "bidirectional"))
      (node (ref "V5") (pin "P$1") (pinfunction "P$1_P$1") (pintype "bidirectional"))
    )
    (net (code "120") (name "SDA") (class "Default")
      (node (ref "R86") (pin "1") (pinfunction "1_1") (pintype "passive"))
      (node (ref "U1") (pin "P$23") (pinfunction "SDA_P$23") (pintype "bidirectional"))
      (node (ref "U2") (pin "P$2") (pinfunction "SDA_P$2") (pintype "bidirectional"))
      (node (ref "V6") (pin "P$1") (pinfunction "P$1_P$1") (pintype "bidirectional"))
    )
    (net (code "121") (name "SPF_ST") (class "Default")
      (node (ref "R83") (pin "1") (pinfunction "1_1") (pintype "passive"))
      (node (ref "U1") (pin "P$6") (pinfunction "P02_P$6") (pintype "bidirectional"))
      (node (ref "U3") (pin "P$4") (pinfunction "STAT_P$4") (pintype "bidirectional"))
    )
    (net (code "122") (name "SP_C") (class "Default")
      (node (ref "C3") (pin "1") (pinfunction "P$1_1") (pintype "passive"))
      (node (ref "M1") (pin "P$5") (pinfunction "D_P$5") (pintype "bidirectional"))
      (node (ref "M1") (pin "P$6") (pinfunction "D_P$6") (pintype "bidirectional"))
      (node (ref "M1") (pin "P$7") (pinfunction "D_P$7") (pintype "bidirectional"))
      (node (ref "M1") (pin "P$8") (pinfunction "D_P$8") (pintype "bidirectional"))
      (node (ref "U3") (pin "P$1") (pinfunction "VIN_P$1") (pintype "bidirectional"))
      (node (ref "V13") (pin "P$1") (pinfunction "P$1_P$1") (pintype "bidirectional"))
      (node (ref "V14") (pin "P$1") (pinfunction "P$1_P$1") (pintype "bidirectional"))
      (node (ref "V15") (pin "P$1") (pinfunction "P$1_P$1") (pintype "bidirectional"))
      (node (ref "V16") (pin "P$1") (pinfunction "P$1_P$1") (pintype "bidirectional"))
      (node (ref "V17") (pin "P$1") (pinfunction "P$1_P$1") (pintype "bidirectional"))
      (node (ref "V18") (pin "P$1") (pinfunction "P$1_P$1") (pintype "bidirectional"))
    )
    (net (code "123") (name "SP_OUT") (class "Default")
      (node (ref "C17") (pin "1") (pinfunction "P$1_1") (pintype "passive"))
      (node (ref "C18") (pin "1") (pinfunction "P$1_1") (pintype "passive"))
      (node (ref "C4") (pin "1") (pinfunction "P$1_1") (pintype "passive"))
      (node (ref "D1") (pin "C") (pinfunction "C_C") (pintype "bidirectional"))
      (node (ref "D6") (pin "A") (pinfunction "A_A") (pintype "bidirectional"))
      (node (ref "D7") (pin "A") (pinfunction "A_A") (pintype "bidirectional"))
      (node (ref "D8") (pin "A") (pinfunction "A_A") (pintype "bidirectional"))
      (node (ref "D9") (pin "A") (pinfunction "A_A") (pintype "bidirectional"))
      (node (ref "M1") (pin "P$1") (pinfunction "S_P$1") (pintype "bidirectional"))
      (node (ref "M1") (pin "P$2") (pinfunction "S_P$2") (pintype "bidirectional"))
      (node (ref "M1") (pin "P$3") (pinfunction "S_P$3") (pintype "bidirectional"))
      (node (ref "R13") (pin "2") (pinfunction "2_2") (pintype "passive"))
      (node (ref "U10") (pin "P$5") (pinfunction "~{SHDN}_P$5") (pintype "bidirectional"))
      (node (ref "U10") (pin "P$8") (pinfunction "IN_P$8") (pintype "bidirectional"))
      (node (ref "U11") (pin "P$5") (pinfunction "~{SHDN}_P$5") (pintype "bidirectional"))
      (node (ref "U11") (pin "P$8") (pinfunction "IN_P$8") (pintype "bidirectional"))
      (node (ref "U3") (pin "P$6") (pinfunction "SNS_P$6") (pintype "bidirectional"))
    )
    (net (code "124") (name "UMB_CHG") (class "Default")
      (node (ref "D1") (pin "A") (pinfunction "A_A") (pintype "bidirectional"))
      (node (ref "V19") (pin "P$1") (pinfunction "P$1_P$1") (pintype "bidirectional"))
    )
    (net (code "125") (name "~{BATT_INT}") (class "Default")
      (node (ref "R84") (pin "1") (pinfunction "1_1") (pintype "passive"))
      (node (ref "U1") (pin "P$1") (pinfunction "~{INT}_P$1") (pintype "bidirectional"))
    )
  )
)
